# 4040M_v1_0.net
KiCad netlist of a schematic drawn in EasyEDA Pro
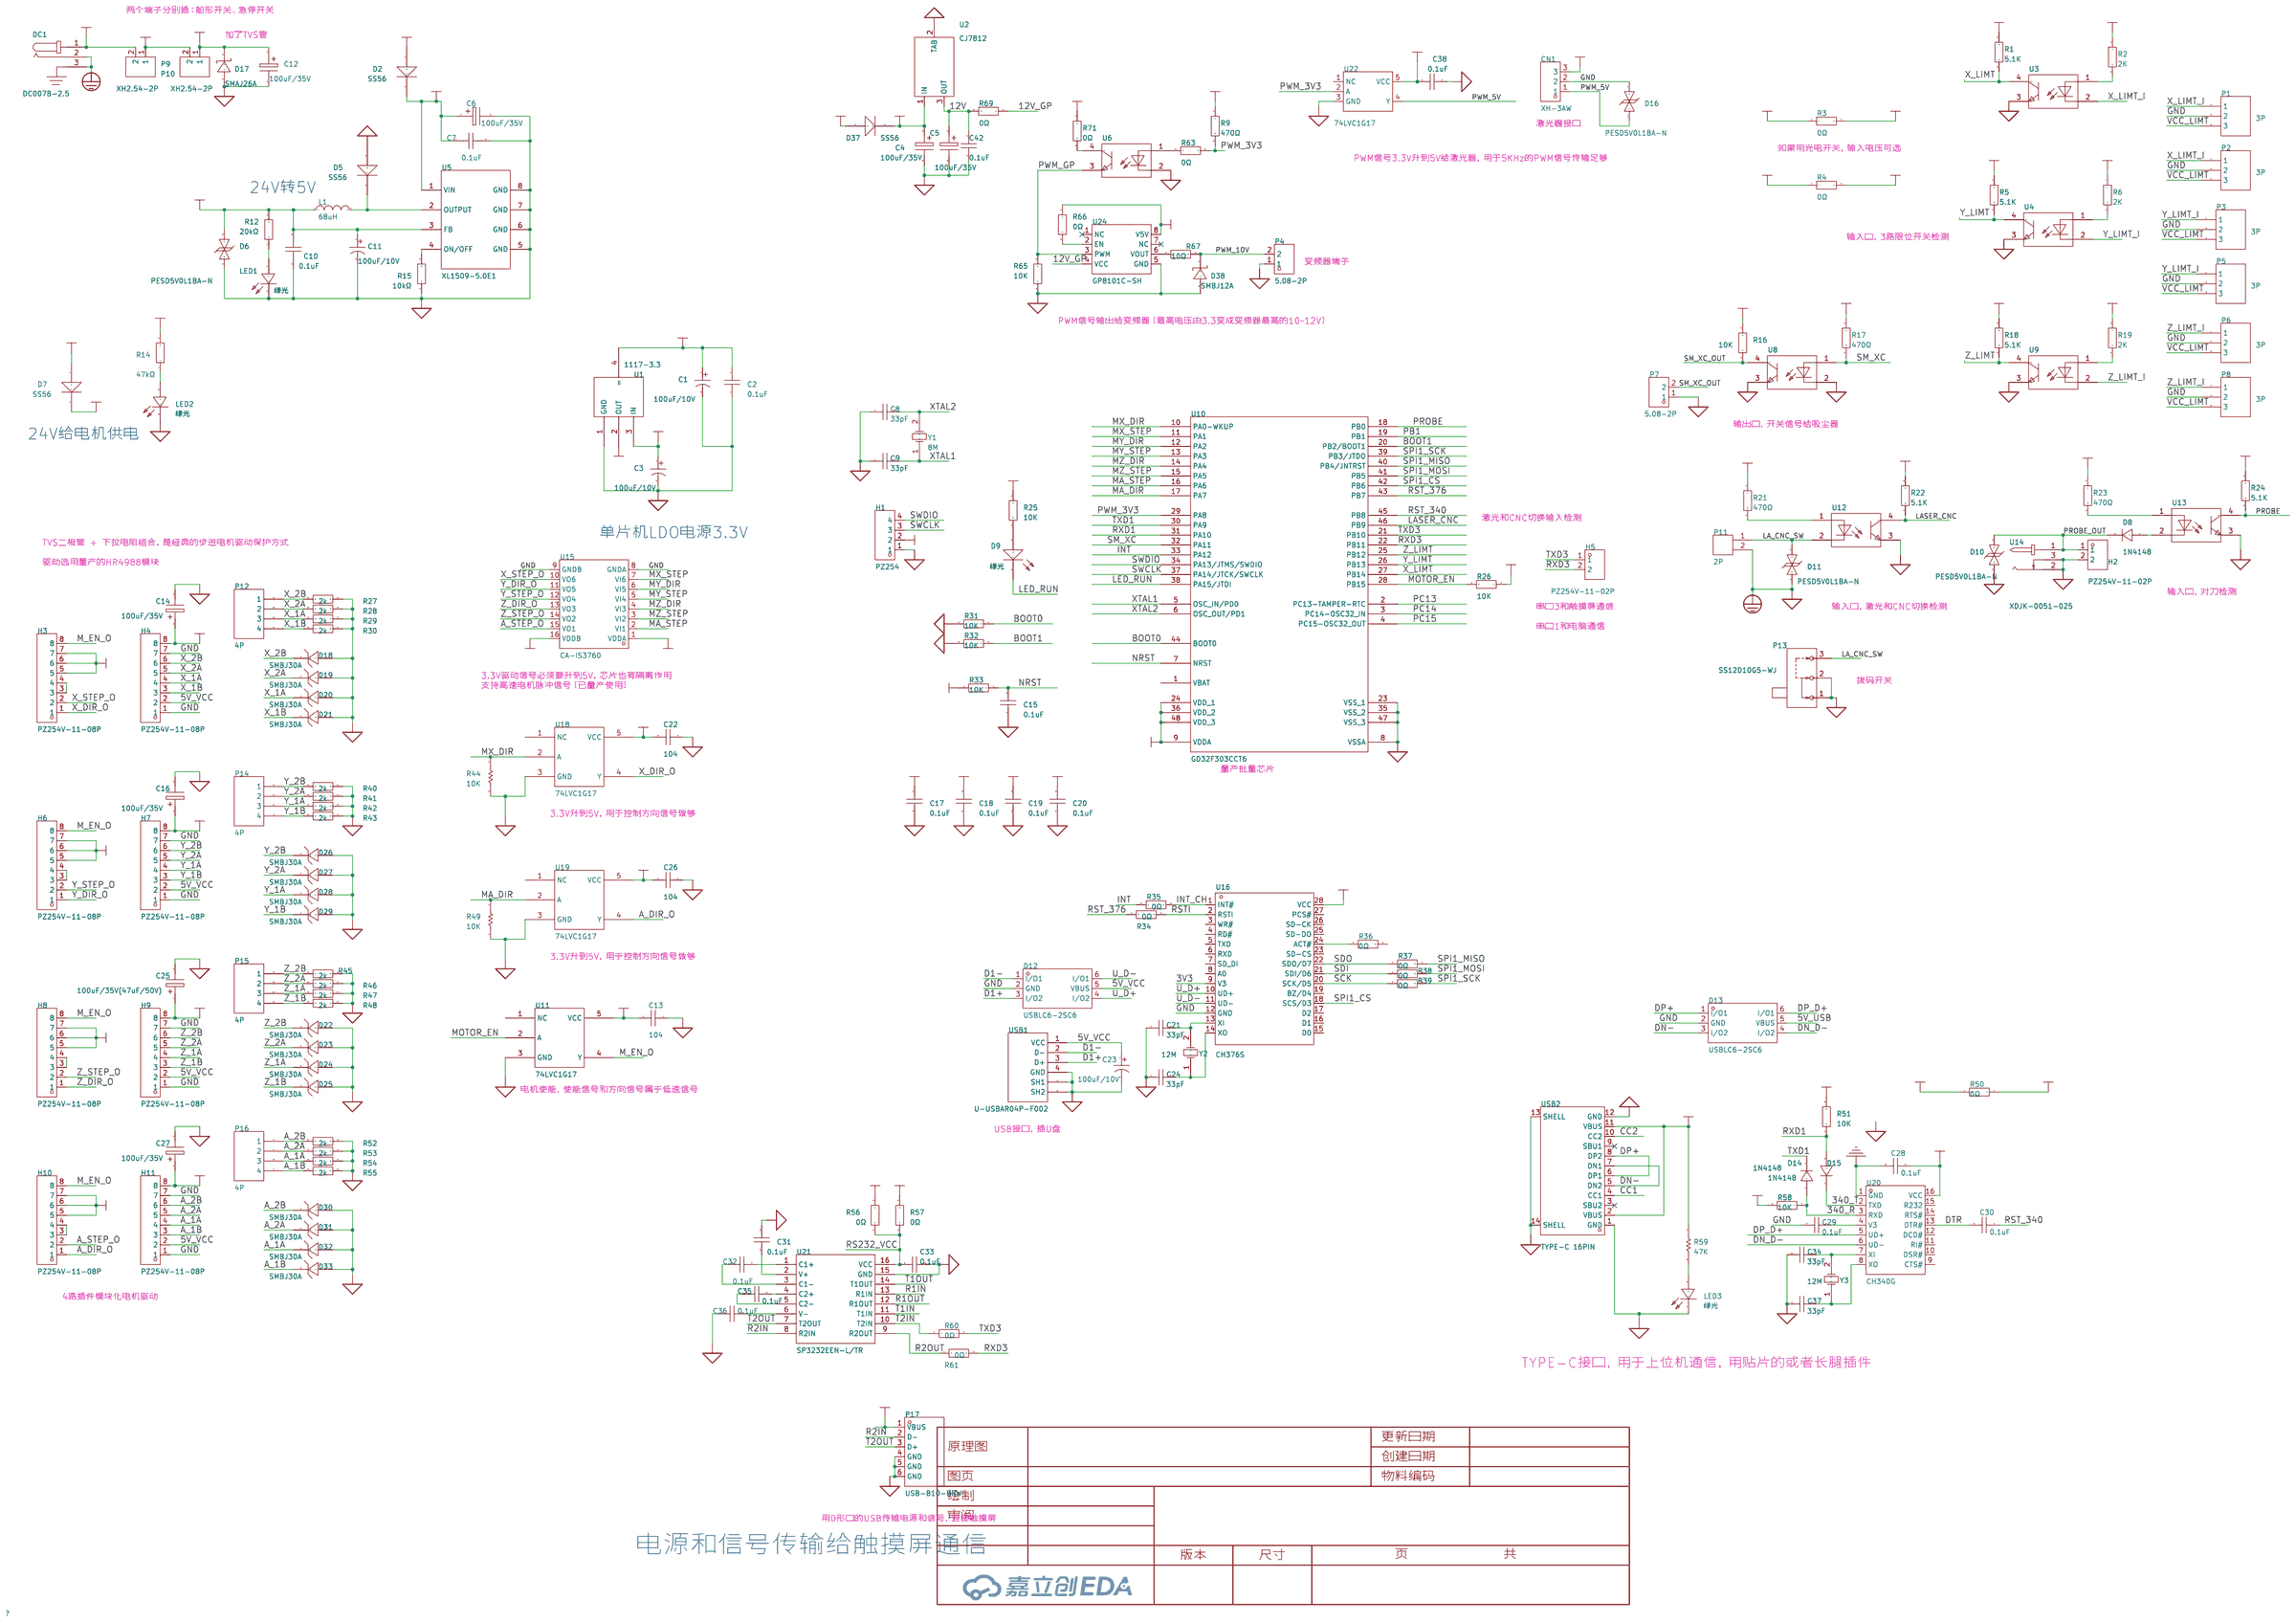
[diagram p0: schematic sheet]

(export (version "E")
  (design (tool "Eeschema 10.0.6"))
  (components
    (comp (ref "C1")
      (value "100uF/10V")
      (footprint "easyedapro:CAP-SMD_BD5.0-L5.3-W5.3-RD")
      (fields (field (name "Manufacturer Part") "CS1A101M-CRD54") (field (name "Manufacturer") "ST(先科)"))
      (libsource (lib "easyedapro") (part "CS1A101M-CRD54"))
    )
    (comp (ref "C2")
      (value "0.1uF")
      (footprint "easyedapro:C0603")
      (description "容值:6.8nF;精度:±10%;额定电压:50V;温度系数:X7R;")
      (fields (field (name "Manufacturer Part") "0603B682K500NT") (field (name "Manufacturer") "FH(风华)"))
      (libsource (lib "easyedapro") (part "0603B682K500NT"))
    )
    (comp (ref "C3")
      (value "100uF/10V")
      (footprint "easyedapro:CAP-SMD_BD5.0-L5.3-W5.3-RD")
      (fields (field (name "Manufacturer Part") "CS1A101M-CRD54") (field (name "Manufacturer") "ST(先科)"))
      (libsource (lib "easyedapro") (part "CS1A101M-CRD54"))
    )
    (comp (ref "C4")
      (value "100uF/35V")
      (footprint "easyedapro:电解电容贴片10x10")
      (libsource (lib "easyedapro") (part "ELECTRO1"))
    )
    (comp (ref "C5")
      (value "100uF/35V")
      (footprint "easyedapro:电解电容贴片10x10")
      (libsource (lib "easyedapro") (part "ELECTRO1"))
    )
    (comp (ref "C6")
      (value "100uF/35V")
      (footprint "easyedapro:电解电容贴片10x10")
      (libsource (lib "easyedapro") (part "ELECTRO1"))
    )
    (comp (ref "C7")
      (value "0.1uF")
      (footprint "easyedapro:C0603")
      (description "容值:8.2nF;精度:±10%;额定电压:50V;温度系数:X7R;")
      (fields (field (name "Manufacturer Part") "0603B822K500NT") (field (name "Manufacturer") "FH(风华)"))
      (libsource (lib "easyedapro") (part "0603B822K500NT"))
    )
    (comp (ref "C8")
      (value "33pF")
      (footprint "easyedapro:C0603")
      (description "容值:12pF;精度:±5%;额定电压:50V;温度系数:C0G;")
      (fields
        (field (name "Manufacturer Part") "CL10C120JB8NNNC")
        (field (name "Manufacturer") "SAMSUNG(三星)")
      )
      (libsource (lib "easyedapro") (part "CL10C120JB8NNNC"))
    )
    (comp (ref "C9")
      (value "33pF")
      (footprint "easyedapro:C0603")
      (description "容值:12pF;精度:±5%;额定电压:50V;温度系数:C0G;")
      (fields
        (field (name "Manufacturer Part") "CL10C120JB8NNNC")
        (field (name "Manufacturer") "SAMSUNG(三星)")
      )
      (libsource (lib "easyedapro") (part "CL10C120JB8NNNC"))
    )
    (comp (ref "C10")
      (value "0.1uF")
      (footprint "easyedapro:C0603")
      (description "容值:8.2nF;精度:±10%;额定电压:50V;温度系数:X7R;")
      (fields (field (name "Manufacturer Part") "0603B822K500NT") (field (name "Manufacturer") "FH(风华)"))
      (libsource (lib "easyedapro") (part "0603B822K500NT"))
    )
    (comp (ref "C11")
      (value "100uF/10V")
      (footprint "easyedapro:CAP-SMD_BD5.0-L5.3-W5.3-RD")
      (fields (field (name "Manufacturer Part") "CS1A101M-CRD54") (field (name "Manufacturer") "ST(先科)"))
      (libsource (lib "easyedapro") (part "CS1A101M-CRD54"))
    )
    (comp (ref "C12")
      (value "100uF/35V")
      (footprint "easyedapro:电解电容贴片10x10")
      (libsource (lib "easyedapro") (part "ELECTRO1"))
    )
    (comp (ref "C13")
      (value "104")
      (footprint "easyedapro:0603C")
      (description "Capacitor (Semiconductor SIM Model)")
      (libsource (lib "easyedapro") (part "Cap Semi"))
    )
    (comp (ref "C14")
      (value "100uF/35V")
      (footprint "easyedapro:电解电容贴片10x10")
      (libsource (lib "easyedapro") (part "ELECTRO1"))
    )
    (comp (ref "C15")
      (value "0.1uF")
      (footprint "easyedapro:C0603")
      (description "容值:6.8nF;精度:±10%;额定电压:50V;温度系数:X7R;")
      (fields (field (name "Manufacturer Part") "0603B682K500NT") (field (name "Manufacturer") "FH(风华)"))
      (libsource (lib "easyedapro") (part "0603B682K500NT"))
    )
    (comp (ref "C16")
      (value "100uF/35V")
      (footprint "easyedapro:电解电容贴片10x10")
      (libsource (lib "easyedapro") (part "ELECTRO1"))
    )
    (comp (ref "C17")
      (value "0.1uF")
      (footprint "easyedapro:C0603")
      (description "容值:6.8nF;精度:±10%;额定电压:50V;温度系数:X7R;")
      (fields (field (name "Manufacturer Part") "0603B682K500NT") (field (name "Manufacturer") "FH(风华)"))
      (libsource (lib "easyedapro") (part "0603B682K500NT"))
    )
    (comp (ref "C18")
      (value "0.1uF")
      (footprint "easyedapro:C0603")
      (description "容值:6.8nF;精度:±10%;额定电压:50V;温度系数:X7R;")
      (fields (field (name "Manufacturer Part") "0603B682K500NT") (field (name "Manufacturer") "FH(风华)"))
      (libsource (lib "easyedapro") (part "0603B682K500NT"))
    )
    (comp (ref "C19")
      (value "0.1uF")
      (footprint "easyedapro:C0603")
      (description "容值:6.8nF;精度:±10%;额定电压:50V;温度系数:X7R;")
      (fields (field (name "Manufacturer Part") "0603B682K500NT") (field (name "Manufacturer") "FH(风华)"))
      (libsource (lib "easyedapro") (part "0603B682K500NT"))
    )
    (comp (ref "C20")
      (value "0.1uF")
      (footprint "easyedapro:C0603")
      (description "容值:6.8nF;精度:±10%;额定电压:50V;温度系数:X7R;")
      (fields (field (name "Manufacturer Part") "0603B682K500NT") (field (name "Manufacturer") "FH(风华)"))
      (libsource (lib "easyedapro") (part "0603B682K500NT"))
    )
    (comp (ref "C21")
      (value "33pF")
      (footprint "easyedapro:C0603")
      (description "容值:12pF;精度:±5%;额定电压:50V;温度系数:C0G;")
      (fields
        (field (name "Manufacturer Part") "CL10C120JB8NNNC")
        (field (name "Manufacturer") "SAMSUNG(三星)")
      )
      (libsource (lib "easyedapro") (part "CL10C120JB8NNNC"))
    )
    (comp (ref "C22")
      (value "104")
      (footprint "easyedapro:0603C")
      (description "Capacitor (Semiconductor SIM Model)")
      (libsource (lib "easyedapro") (part "Cap Semi"))
    )
    (comp (ref "C23")
      (value "100uF/10V")
      (footprint "easyedapro:CAP-SMD_BD5.0-L5.3-W5.3-RD")
      (fields (field (name "Manufacturer Part") "CS1A101M-CRD54") (field (name "Manufacturer") "ST(先科)"))
      (libsource (lib "easyedapro") (part "CS1A101M-CRD54"))
    )
    (comp (ref "C24")
      (value "33pF")
      (footprint "easyedapro:C0603")
      (description "容值:12pF;精度:±5%;额定电压:50V;温度系数:C0G;")
      (fields
        (field (name "Manufacturer Part") "CL10C120JB8NNNC")
        (field (name "Manufacturer") "SAMSUNG(三星)")
      )
      (libsource (lib "easyedapro") (part "CL10C120JB8NNNC"))
    )
    (comp (ref "C25")
      (value "100uF/35V(47uF/50V)")
      (footprint "easyedapro:电解电容贴片10x10")
      (libsource (lib "easyedapro") (part "ELECTRO1"))
    )
    (comp (ref "C26")
      (value "104")
      (footprint "easyedapro:0603C")
      (description "Capacitor (Semiconductor SIM Model)")
      (libsource (lib "easyedapro") (part "Cap Semi"))
    )
    (comp (ref "C27")
      (value "100uF/35V")
      (footprint "easyedapro:电解电容贴片10x10")
      (libsource (lib "easyedapro") (part "ELECTRO1"))
    )
    (comp (ref "C28")
      (value "0.1uF")
      (footprint "easyedapro:C0603")
      (description "容值:6.8nF;精度:±10%;额定电压:50V;温度系数:X7R;")
      (fields (field (name "Manufacturer Part") "0603B682K500NT") (field (name "Manufacturer") "FH(风华)"))
      (libsource (lib "easyedapro") (part "0603B682K500NT"))
    )
    (comp (ref "C29")
      (value "0.1uF")
      (footprint "easyedapro:C0603")
      (description "容值:6.8nF;精度:±10%;额定电压:50V;温度系数:X7R;")
      (fields (field (name "Manufacturer Part") "0603B682K500NT") (field (name "Manufacturer") "FH(风华)"))
      (libsource (lib "easyedapro") (part "0603B682K500NT"))
    )
    (comp (ref "C30")
      (value "0.1uF")
      (footprint "easyedapro:C0603")
      (description "容值:6.8nF;精度:±10%;额定电压:50V;温度系数:X7R;")
      (fields (field (name "Manufacturer Part") "0603B682K500NT") (field (name "Manufacturer") "FH(风华)"))
      (libsource (lib "easyedapro") (part "0603B682K500NT"))
    )
    (comp (ref "C31")
      (value "0.1uF")
      (footprint "easyedapro:C0603")
      (description "容值:6.8nF;精度:±10%;额定电压:50V;温度系数:X7R;")
      (fields (field (name "Manufacturer Part") "0603B682K500NT") (field (name "Manufacturer") "FH(风华)"))
      (libsource (lib "easyedapro") (part "0603B682K500NT"))
    )
    (comp (ref "C32")
      (value "0.1uF")
      (footprint "easyedapro:C0603")
      (description "容值:6.8nF;精度:±10%;额定电压:50V;温度系数:X7R;")
      (fields (field (name "Manufacturer Part") "0603B682K500NT") (field (name "Manufacturer") "FH(风华)"))
      (libsource (lib "easyedapro") (part "0603B682K500NT"))
    )
    (comp (ref "C33")
      (value "0.1uF")
      (footprint "easyedapro:C0603")
      (description "容值:6.8nF;精度:±10%;额定电压:50V;温度系数:X7R;")
      (fields (field (name "Manufacturer Part") "0603B682K500NT") (field (name "Manufacturer") "FH(风华)"))
      (libsource (lib "easyedapro") (part "0603B682K500NT"))
    )
    (comp (ref "C34")
      (value "33pF")
      (footprint "easyedapro:C0603")
      (description "容值:12pF;精度:±5%;额定电压:50V;温度系数:C0G;")
      (fields
        (field (name "Manufacturer Part") "CL10C120JB8NNNC")
        (field (name "Manufacturer") "SAMSUNG(三星)")
      )
      (libsource (lib "easyedapro") (part "CL10C120JB8NNNC"))
    )
    (comp (ref "C35")
      (value "0.1uF")
      (footprint "easyedapro:C0603")
      (description "容值:6.8nF;精度:±10%;额定电压:50V;温度系数:X7R;")
      (fields (field (name "Manufacturer Part") "0603B682K500NT") (field (name "Manufacturer") "FH(风华)"))
      (libsource (lib "easyedapro") (part "0603B682K500NT"))
    )
    (comp (ref "C36")
      (value "0.1uF")
      (footprint "easyedapro:C0603")
      (description "容值:6.8nF;精度:±10%;额定电压:50V;温度系数:X7R;")
      (fields (field (name "Manufacturer Part") "0603B682K500NT") (field (name "Manufacturer") "FH(风华)"))
      (libsource (lib "easyedapro") (part "0603B682K500NT"))
    )
    (comp (ref "C37")
      (value "33pF")
      (footprint "easyedapro:C0603")
      (description "容值:12pF;精度:±5%;额定电压:50V;温度系数:C0G;")
      (fields
        (field (name "Manufacturer Part") "CL10C120JB8NNNC")
        (field (name "Manufacturer") "SAMSUNG(三星)")
      )
      (libsource (lib "easyedapro") (part "CL10C120JB8NNNC"))
    )
    (comp (ref "C38")
      (value "0.1uF")
      (footprint "easyedapro:C0603")
      (description "容值:6.8nF;精度:±10%;额定电压:50V;温度系数:X7R;")
      (fields (field (name "Manufacturer Part") "0603B682K500NT") (field (name "Manufacturer") "FH(风华)"))
      (libsource (lib "easyedapro") (part "0603B682K500NT"))
    )
    (comp (ref "C42")
      (value "0.1uF")
      (footprint "easyedapro:C0603")
      (description "容值:6.8nF;精度:±10%;额定电压:50V;温度系数:X7R;")
      (fields (field (name "Manufacturer Part") "0603B682K500NT") (field (name "Manufacturer") "FH(风华)"))
      (libsource (lib "easyedapro") (part "0603B682K500NT"))
    )
    (comp (ref "CN1")
      (value "XH-3AW")
      (footprint "easyedapro:CONN-TH_3P-P2.54_HCTL_XH-3AW")
      (fields (field (name "Manufacturer") "HCTL(华灿天禄)"))
      (libsource (lib "easyedapro") (part "XH-3AW_C2908612"))
    )
    (comp (ref "D2")
      (value "SS56")
      (footprint "easyedapro:SMA")
      (libsource (lib "easyedapro") (part "1N4148"))
    )
    (comp (ref "D5")
      (value "SS56")
      (footprint "easyedapro:SMA")
      (libsource (lib "easyedapro") (part "1N4148"))
    )
    (comp (ref "D6")
      (value "PESD5V0L1BA-N")
      (footprint "easyedapro:SOD-523_L1.2-W0.8-LS1.6-BI")
      (description "极性:Bidirectional;反向关断电压（典型值）:5V (Max);击穿电压（最小值）:6V;箝位电压:15V;峰值脉冲电流（10/1000us）:5A (8/20us);")
      (fields (field (name "Manufacturer") "BORN伯恩半导体"))
      (libsource (lib "easyedapro") (part "PESD5V0S1BBN"))
    )
    (comp (ref "D7")
      (value "SS56")
      (footprint "easyedapro:SMA")
      (libsource (lib "easyedapro") (part "1N4148"))
    )
    (comp (ref "D8")
      (value "1N4148")
      (footprint "easyedapro:SOD-323_L1.8-W1.3-LS2.5-RD")
      (description "二极管配置:独立式;正向压降(Vf):1.25V@150mA;直流反向耐压(Vr):100V;整流电流:150mA;反向恢复时间(Trr):4ns;")
      (fields (field (name "Manufacturer") "CJ(江苏长电/长晶)"))
      (libsource (lib "easyedapro") (part "1N4148WS T4"))
    )
    (comp (ref "D9")
      (value "绿光")
      (footprint "easyedapro:0603LED")
      (libsource (lib "easyedapro") (part "LED"))
    )
    (comp (ref "D10")
      (value "PESD5V0L1BA-N")
      (footprint "easyedapro:SOD-523_L1.2-W0.8-LS1.6-BI")
      (description "极性:Bidirectional;反向关断电压（典型值）:5V (Max);击穿电压（最小值）:6V;箝位电压:15V;峰值脉冲电流（10/1000us）:5A (8/20us);")
      (fields (field (name "Manufacturer") "BORN伯恩半导体"))
      (libsource (lib "easyedapro") (part "PESD5V0S1BBN"))
    )
    (comp (ref "D11")
      (value "PESD5V0L1BA-N")
      (footprint "easyedapro:SOD-523_L1.2-W0.8-LS1.6-BI")
      (description "极性:Bidirectional;反向关断电压（典型值）:5V (Max);击穿电压（最小值）:6V;箝位电压:15V;峰值脉冲电流（10/1000us）:5A (8/20us);")
      (fields (field (name "Manufacturer") "BORN伯恩半导体"))
      (libsource (lib "easyedapro") (part "PESD5V0S1BBN"))
    )
    (comp (ref "D12")
      (value "USBLC6-2SC6")
      (footprint "easyedapro:SOT-23-6_L2.9-W1.6-P0.95-LS2.8-BL")
      (description "最大钳位电压:15V;击穿电压:6V;")
      (fields (field (name "Manufacturer") "UMW(友台半导体)"))
      (libsource (lib "easyedapro") (part "USBLC6-2SC6_C2687116"))
    )
    (comp (ref "D13")
      (value "USBLC6-2SC6")
      (footprint "easyedapro:SOT-23-6_L2.9-W1.6-P0.95-LS2.8-BL")
      (description "最大钳位电压:15V;击穿电压:6V;")
      (fields (field (name "Manufacturer") "UMW(友台半导体)"))
      (libsource (lib "easyedapro") (part "USBLC6-2SC6_C2687116"))
    )
    (comp (ref "D14")
      (value "1N4148")
      (footprint "easyedapro:SOD-323_L1.8-W1.3-LS2.5-RD")
      (description "二极管配置:独立式;正向压降(Vf):1.25V@150mA;直流反向耐压(Vr):100V;整流电流:150mA;反向恢复时间(Trr):4ns;")
      (fields (field (name "Manufacturer") "CJ(江苏长电/长晶)"))
      (libsource (lib "easyedapro") (part "1N4148WS T4"))
    )
    (comp (ref "D15")
      (value "1N4148")
      (footprint "easyedapro:SOD-323_L1.8-W1.3-LS2.5-RD")
      (description "二极管配置:独立式;正向压降(Vf):1.25V@150mA;直流反向耐压(Vr):100V;整流电流:150mA;反向恢复时间(Trr):4ns;")
      (fields (field (name "Manufacturer") "CJ(江苏长电/长晶)"))
      (libsource (lib "easyedapro") (part "1N4148WS T4"))
    )
    (comp (ref "D16")
      (value "PESD5V0L1BA-N")
      (footprint "easyedapro:SOD-523_L1.2-W0.8-LS1.6-BI")
      (description "极性:Bidirectional;反向关断电压（典型值）:5V (Max);击穿电压（最小值）:6V;箝位电压:15V;峰值脉冲电流（10/1000us）:5A (8/20us);")
      (fields (field (name "Manufacturer") "BORN伯恩半导体"))
      (libsource (lib "easyedapro") (part "PESD5V0S1BBN"))
    )
    (comp (ref "D17")
      (value "SMAJ26A")
      (footprint "easyedapro:SMA_L4.4-W2.8-LS5.1-RD")
      (description "反向截止电压(Vrwm):26V;最大钳位电压:42.1V;峰值脉冲电流(Ipp):9.5A;击穿电压:28.9V;")
      (fields (field (name "Manufacturer") "JJW(捷捷微)"))
      (libsource (lib "easyedapro") (part "SMAJ26A_C356747"))
    )
    (comp (ref "D18")
      (value "SMBJ30A")
      (footprint "easyedapro:SMB_L4.6-W3.6-LS5.3-RD")
      (description "反向截止电压(Vrwm):30V;最大钳位电压:48.4V;峰值脉冲电流(Ipp):12.4A;击穿电压:33.3V;")
      (fields (field (name "Manufacturer") "GOOD-ARK(固锝)"))
      (libsource (lib "easyedapro") (part "SMBJ30A_C266337"))
    )
    (comp (ref "D19")
      (value "SMBJ30A")
      (footprint "easyedapro:SMB_L4.6-W3.6-LS5.3-RD")
      (description "反向截止电压(Vrwm):30V;最大钳位电压:48.4V;峰值脉冲电流(Ipp):12.4A;击穿电压:33.3V;")
      (fields (field (name "Manufacturer") "GOOD-ARK(固锝)"))
      (libsource (lib "easyedapro") (part "SMBJ30A_C266337"))
    )
    (comp (ref "D20")
      (value "SMBJ30A")
      (footprint "easyedapro:SMB_L4.6-W3.6-LS5.3-RD")
      (description "反向截止电压(Vrwm):30V;最大钳位电压:48.4V;峰值脉冲电流(Ipp):12.4A;击穿电压:33.3V;")
      (fields (field (name "Manufacturer") "GOOD-ARK(固锝)"))
      (libsource (lib "easyedapro") (part "SMBJ30A_C266337"))
    )
    (comp (ref "D21")
      (value "SMBJ30A")
      (footprint "easyedapro:SMB_L4.6-W3.6-LS5.3-RD")
      (description "反向截止电压(Vrwm):30V;最大钳位电压:48.4V;峰值脉冲电流(Ipp):12.4A;击穿电压:33.3V;")
      (fields (field (name "Manufacturer") "GOOD-ARK(固锝)"))
      (libsource (lib "easyedapro") (part "SMBJ30A_C266337"))
    )
    (comp (ref "D22")
      (value "SMBJ30A")
      (footprint "easyedapro:SMB_L4.6-W3.6-LS5.3-RD")
      (description "反向截止电压(Vrwm):30V;最大钳位电压:48.4V;峰值脉冲电流(Ipp):12.4A;击穿电压:33.3V;")
      (fields (field (name "Manufacturer") "GOOD-ARK(固锝)"))
      (libsource (lib "easyedapro") (part "SMBJ30A_C266337"))
    )
    (comp (ref "D23")
      (value "SMBJ30A")
      (footprint "easyedapro:SMB_L4.6-W3.6-LS5.3-RD")
      (description "反向截止电压(Vrwm):30V;最大钳位电压:48.4V;峰值脉冲电流(Ipp):12.4A;击穿电压:33.3V;")
      (fields (field (name "Manufacturer") "GOOD-ARK(固锝)"))
      (libsource (lib "easyedapro") (part "SMBJ30A_C266337"))
    )
    (comp (ref "D24")
      (value "SMBJ30A")
      (footprint "easyedapro:SMB_L4.6-W3.6-LS5.3-RD")
      (description "反向截止电压(Vrwm):30V;最大钳位电压:48.4V;峰值脉冲电流(Ipp):12.4A;击穿电压:33.3V;")
      (fields (field (name "Manufacturer") "GOOD-ARK(固锝)"))
      (libsource (lib "easyedapro") (part "SMBJ30A_C266337"))
    )
    (comp (ref "D25")
      (value "SMBJ30A")
      (footprint "easyedapro:SMB_L4.6-W3.6-LS5.3-RD")
      (description "反向截止电压(Vrwm):30V;最大钳位电压:48.4V;峰值脉冲电流(Ipp):12.4A;击穿电压:33.3V;")
      (fields (field (name "Manufacturer") "GOOD-ARK(固锝)"))
      (libsource (lib "easyedapro") (part "SMBJ30A_C266337"))
    )
    (comp (ref "D26")
      (value "SMBJ30A")
      (footprint "easyedapro:SMB_L4.6-W3.6-LS5.3-RD")
      (description "反向截止电压(Vrwm):30V;最大钳位电压:48.4V;峰值脉冲电流(Ipp):12.4A;击穿电压:33.3V;")
      (fields (field (name "Manufacturer") "GOOD-ARK(固锝)"))
      (libsource (lib "easyedapro") (part "SMBJ30A_C266337"))
    )
    (comp (ref "D27")
      (value "SMBJ30A")
      (footprint "easyedapro:SMB_L4.6-W3.6-LS5.3-RD")
      (description "反向截止电压(Vrwm):30V;最大钳位电压:48.4V;峰值脉冲电流(Ipp):12.4A;击穿电压:33.3V;")
      (fields (field (name "Manufacturer") "GOOD-ARK(固锝)"))
      (libsource (lib "easyedapro") (part "SMBJ30A_C266337"))
    )
    (comp (ref "D28")
      (value "SMBJ30A")
      (footprint "easyedapro:SMB_L4.6-W3.6-LS5.3-RD")
      (description "反向截止电压(Vrwm):30V;最大钳位电压:48.4V;峰值脉冲电流(Ipp):12.4A;击穿电压:33.3V;")
      (fields (field (name "Manufacturer") "GOOD-ARK(固锝)"))
      (libsource (lib "easyedapro") (part "SMBJ30A_C266337"))
    )
    (comp (ref "D29")
      (value "SMBJ30A")
      (footprint "easyedapro:SMB_L4.6-W3.6-LS5.3-RD")
      (description "反向截止电压(Vrwm):30V;最大钳位电压:48.4V;峰值脉冲电流(Ipp):12.4A;击穿电压:33.3V;")
      (fields (field (name "Manufacturer") "GOOD-ARK(固锝)"))
      (libsource (lib "easyedapro") (part "SMBJ30A_C266337"))
    )
    (comp (ref "D30")
      (value "SMBJ30A")
      (footprint "easyedapro:SMB_L4.6-W3.6-LS5.3-RD")
      (description "反向截止电压(Vrwm):30V;最大钳位电压:48.4V;峰值脉冲电流(Ipp):12.4A;击穿电压:33.3V;")
      (fields (field (name "Manufacturer") "GOOD-ARK(固锝)"))
      (libsource (lib "easyedapro") (part "SMBJ30A_C266337"))
    )
    (comp (ref "D31")
      (value "SMBJ30A")
      (footprint "easyedapro:SMB_L4.6-W3.6-LS5.3-RD")
      (description "反向截止电压(Vrwm):30V;最大钳位电压:48.4V;峰值脉冲电流(Ipp):12.4A;击穿电压:33.3V;")
      (fields (field (name "Manufacturer") "GOOD-ARK(固锝)"))
      (libsource (lib "easyedapro") (part "SMBJ30A_C266337"))
    )
    (comp (ref "D32")
      (value "SMBJ30A")
      (footprint "easyedapro:SMB_L4.6-W3.6-LS5.3-RD")
      (description "反向截止电压(Vrwm):30V;最大钳位电压:48.4V;峰值脉冲电流(Ipp):12.4A;击穿电压:33.3V;")
      (fields (field (name "Manufacturer") "GOOD-ARK(固锝)"))
      (libsource (lib "easyedapro") (part "SMBJ30A_C266337"))
    )
    (comp (ref "D33")
      (value "SMBJ30A")
      (footprint "easyedapro:SMB_L4.6-W3.6-LS5.3-RD")
      (description "反向截止电压(Vrwm):30V;最大钳位电压:48.4V;峰值脉冲电流(Ipp):12.4A;击穿电压:33.3V;")
      (fields (field (name "Manufacturer") "GOOD-ARK(固锝)"))
      (libsource (lib "easyedapro") (part "SMBJ30A_C266337"))
    )
    (comp (ref "D37")
      (value "SS56")
      (footprint "easyedapro:SMA")
      (libsource (lib "easyedapro") (part "1N4148"))
    )
    (comp (ref "D38")
      (value "SMBJ12A")
      (footprint "easyedapro:SMB_L4.6-W3.6-LS5.4-RD")
      (description "反向截止电压(Vrwm):12V;最大钳位电压:19.9V;峰值脉冲电流(Ipp):30.2A;击穿电压:13.3V;")
      (fields (field (name "Manufacturer") "JJW(捷捷微)"))
      (libsource (lib "easyedapro") (part "SMBJ12A_C356757"))
    )
    (comp (ref "DC1")
      (value "DC007B-2.5")
      (footprint "easyedapro:DC-IN-TH_HX-DC007B-2.5")
      (description "连接器类型:DC电源插座;安装方式:弯插;触点内径:2.5mm;触点外径:7.7mm;额定电流:5A;额定电压:20V;工作温度:-25°C~+70°C;")
      (fields (field (name "Manufacturer") "SHOU HAN(首韩)"))
      (libsource (lib "easyedapro") (part "DC007B-2.5"))
    )
    (comp (ref "H1")
      (value "PZ254")
      (footprint "easyedapro:HDR-TH_4P-P2.54-V-M")
      (fields (field (name "Manufacturer") "XFCN(兴飞)"))
      (libsource (lib "easyedapro") (part "PZ254V-11-04P_C2691448"))
    )
    (comp (ref "H2")
      (value "PZ254V-11-02P")
      (footprint "easyedapro:HDR-TH_2P-P2.54-V-M")
      (fields (field (name "Manufacturer") "XFCN(兴飞)"))
      (libsource (lib "easyedapro") (part "PZ254V-11-02P"))
    )
    (comp (ref "H3")
      (value "PZ254V-11-08P")
      (footprint "easyedapro:HDR-TH_8P-P2.54-V-M")
      (fields (field (name "Manufacturer") "XFCN(兴飞)"))
      (libsource (lib "easyedapro") (part "PZ254V-11-08P"))
    )
    (comp (ref "H4")
      (value "PZ254V-11-08P")
      (footprint "easyedapro:HDR-TH_8P-P2.54-V-M")
      (fields (field (name "Manufacturer") "XFCN(兴飞)"))
      (libsource (lib "easyedapro") (part "PZ254V-11-08P"))
    )
    (comp (ref "H5")
      (value "PZ254V-11-02P")
      (footprint "easyedapro:HDR-TH_2P-P2.54-V-M")
      (fields (field (name "Manufacturer") "XFCN(兴飞)"))
      (libsource (lib "easyedapro") (part "PZ254V-11-02P"))
    )
    (comp (ref "H6")
      (value "PZ254V-11-08P")
      (footprint "easyedapro:HDR-TH_8P-P2.54-V-M")
      (fields (field (name "Manufacturer") "XFCN(兴飞)"))
      (libsource (lib "easyedapro") (part "PZ254V-11-08P"))
    )
    (comp (ref "H7")
      (value "PZ254V-11-08P")
      (footprint "easyedapro:HDR-TH_8P-P2.54-V-M")
      (fields (field (name "Manufacturer") "XFCN(兴飞)"))
      (libsource (lib "easyedapro") (part "PZ254V-11-08P"))
    )
    (comp (ref "H8")
      (value "PZ254V-11-08P")
      (footprint "easyedapro:HDR-TH_8P-P2.54-V-M")
      (fields (field (name "Manufacturer") "XFCN(兴飞)"))
      (libsource (lib "easyedapro") (part "PZ254V-11-08P"))
    )
    (comp (ref "H9")
      (value "PZ254V-11-08P")
      (footprint "easyedapro:HDR-TH_8P-P2.54-V-M")
      (fields (field (name "Manufacturer") "XFCN(兴飞)"))
      (libsource (lib "easyedapro") (part "PZ254V-11-08P"))
    )
    (comp (ref "H10")
      (value "PZ254V-11-08P")
      (footprint "easyedapro:HDR-TH_8P-P2.54-V-M")
      (fields (field (name "Manufacturer") "XFCN(兴飞)"))
      (libsource (lib "easyedapro") (part "PZ254V-11-08P"))
    )
    (comp (ref "H11")
      (value "PZ254V-11-08P")
      (footprint "easyedapro:HDR-TH_8P-P2.54-V-M")
      (fields (field (name "Manufacturer") "XFCN(兴飞)"))
      (libsource (lib "easyedapro") (part "PZ254V-11-08P"))
    )
    (comp (ref "L1")
      (value "68uH")
      (footprint "easyedapro:IND-SMD_L7.0-W7.0_SMDRI74-330MT")
      (description "电感值:33uH;精度:±20%;额定电流:960mA;饱和电流(Isat):1.8A;类型:屏蔽电感;")
      (fields (field (name "Manufacturer Part") "SMDRI74-330MT") (field (name "Manufacturer") "SXN(顺翔诺)"))
      (libsource (lib "easyedapro") (part "SMDRI74-330MT"))
    )
    (comp (ref "LED1")
      (value "绿光")
      (footprint "easyedapro:LED0603-RD")
      (fields (field (name "Manufacturer") "KENTO"))
      (libsource (lib "easyedapro") (part "KT-0603R"))
    )
    (comp (ref "LED2")
      (value "绿光")
      (footprint "easyedapro:LED0603-RD")
      (fields (field (name "Manufacturer") "KENTO"))
      (libsource (lib "easyedapro") (part "KT-0603R"))
    )
    (comp (ref "LED3")
      (value "绿光")
      (footprint "easyedapro:LED0603-RD")
      (fields (field (name "Manufacturer") "KENTO"))
      (libsource (lib "easyedapro") (part "KT-0603R"))
    )
    (comp (ref "P1")
      (value "3P")
      (footprint "easyedapro:HDR1X3_CON")
      (libsource (lib "easyedapro") (part "3P"))
    )
    (comp (ref "P2")
      (value "3P")
      (footprint "easyedapro:HDR1X3_CON")
      (libsource (lib "easyedapro") (part "3P"))
    )
    (comp (ref "P3")
      (value "3P")
      (footprint "easyedapro:HDR1X3_CON")
      (libsource (lib "easyedapro") (part "3P"))
    )
    (comp (ref "P4")
      (value "5.08-2P")
      (footprint "easyedapro:CONN-TH_KF2EDG15R-5.08-2P")
      (fields (field (name "Manufacturer") "KEFA(科发)"))
      (libsource (lib "easyedapro") (part "KF2EDG15R-5.08-2P"))
    )
    (comp (ref "P5")
      (value "3P")
      (footprint "easyedapro:HDR1X3_CON")
      (libsource (lib "easyedapro") (part "3P"))
    )
    (comp (ref "P6")
      (value "3P")
      (footprint "easyedapro:HDR1X3_CON")
      (libsource (lib "easyedapro") (part "3P"))
    )
    (comp (ref "P7")
      (value "5.08-2P")
      (footprint "easyedapro:CONN-TH_KF2EDG15R-5.08-2P")
      (fields (field (name "Manufacturer") "KEFA(科发)"))
      (libsource (lib "easyedapro") (part "KF2EDG15R-5.08-2P"))
    )
    (comp (ref "P8")
      (value "3P")
      (footprint "easyedapro:HDR1X3_CON")
      (libsource (lib "easyedapro") (part "3P"))
    )
    (comp (ref "P9")
      (value "XH2.54-2P")
      (footprint "easyedapro:CONN-TH_XH2.54-2P")
      (libsource (lib "easyedapro") (part "XH2.54直插座-2P"))
    )
    (comp (ref "P10")
      (value "XH2.54-2P")
      (footprint "easyedapro:CONN-TH_XH2.54-2P")
      (libsource (lib "easyedapro") (part "XH2.54直插座-2P"))
    )
    (comp (ref "P11") (value "2P") (libsource (lib "easyedapro") (part "2P")))
    (comp (ref "P12")
      (value "4P")
      (footprint "easyedapro:HDR1X4_CON")
      (libsource (lib "easyedapro") (part "4P"))
    )
    (comp (ref "P13")
      (value "SS12D10G5-WJ")
      (footprint "easyedapro:SW-TH_3P-SS12D06-1")
      (description "电路结构:单刀双掷;安装方式:弯插;开关颜色:黑色;额定电流:2A;额定电压:125V;工作寿命:3千次;")
      (fields (field (name "Manufacturer") "SHOU HAN(首韩)"))
      (libsource (lib "easyedapro") (part "SS12D10G5-WJ"))
    )
    (comp (ref "P14")
      (value "4P")
      (footprint "easyedapro:HDR1X4_CON")
      (libsource (lib "easyedapro") (part "4P"))
    )
    (comp (ref "P15")
      (value "4P")
      (footprint "easyedapro:HDR1X4_CON")
      (libsource (lib "easyedapro") (part "4P"))
    )
    (comp (ref "P16")
      (value "4P")
      (footprint "easyedapro:HDR1X4_CON")
      (libsource (lib "easyedapro") (part "4P"))
    )
    (comp (ref "P17")
      (value "USB-B10-BRW")
      (footprint "easyedapro:USB-B-TH_USB-B10-BRW")
      (fields (field (name "Manufacturer") "XUNPU(讯普)"))
      (libsource (lib "easyedapro") (part "USB-B10-BRW"))
    )
    (comp (ref "R1")
      (value "47K")
      (footprint "easyedapro:R0603")
      (description "电阻类型:厚膜电阻;阻值:24kΩ;精度:±1%;功率:100mW;工作电压:75V;温度系数:±100ppm/°C;")
      (fields
        (field (name "Manufacturer Part") "0603WAF2402T5E")
        (field (name "Manufacturer") "UNI-ROYAL(厚声)")
      )
      (libsource (lib "easyedapro") (part "0603WAF2402T5E"))
    )
    (comp (ref "R2")
      (value "4.7K")
      (footprint "easyedapro:R0603")
      (description "电阻类型:厚膜电阻;阻值:24kΩ;精度:±1%;功率:100mW;工作电压:75V;温度系数:±100ppm/°C;")
      (fields
        (field (name "Manufacturer Part") "0603WAF2402T5E")
        (field (name "Manufacturer") "UNI-ROYAL(厚声)")
      )
      (libsource (lib "easyedapro") (part "0603WAF2402T5E"))
    )
    (comp (ref "R3")
      (value "0Ω")
      (footprint "easyedapro:R0603")
      (description "电阻类型:厚膜电阻;阻值:24kΩ;精度:±1%;功率:100mW;工作电压:75V;温度系数:±100ppm/°C;")
      (fields
        (field (name "Manufacturer Part") "0603WAF2402T5E")
        (field (name "Manufacturer") "UNI-ROYAL(厚声)")
      )
      (libsource (lib "easyedapro") (part "0603WAF2402T5E"))
    )
    (comp (ref "R4")
      (value "0Ω")
      (footprint "easyedapro:R0603")
      (description "电阻类型:厚膜电阻;阻值:24kΩ;精度:±1%;功率:100mW;工作电压:75V;温度系数:±100ppm/°C;")
      (fields
        (field (name "Manufacturer Part") "0603WAF2402T5E")
        (field (name "Manufacturer") "UNI-ROYAL(厚声)")
      )
      (libsource (lib "easyedapro") (part "0603WAF2402T5E"))
    )
    (comp (ref "R5")
      (value "47K")
      (footprint "easyedapro:R0603")
      (description "电阻类型:厚膜电阻;阻值:24kΩ;精度:±1%;功率:100mW;工作电压:75V;温度系数:±100ppm/°C;")
      (fields
        (field (name "Manufacturer Part") "0603WAF2402T5E")
        (field (name "Manufacturer") "UNI-ROYAL(厚声)")
      )
      (libsource (lib "easyedapro") (part "0603WAF2402T5E"))
    )
    (comp (ref "R6")
      (value "4.7K")
      (footprint "easyedapro:R0603")
      (description "电阻类型:厚膜电阻;阻值:24kΩ;精度:±1%;功率:100mW;工作电压:75V;温度系数:±100ppm/°C;")
      (fields
        (field (name "Manufacturer Part") "0603WAF2402T5E")
        (field (name "Manufacturer") "UNI-ROYAL(厚声)")
      )
      (libsource (lib "easyedapro") (part "0603WAF2402T5E"))
    )
    (comp (ref "R9")
      (value "47K")
      (footprint "easyedapro:R0603")
      (description "电阻类型:厚膜电阻;阻值:24kΩ;精度:±1%;功率:100mW;工作电压:75V;温度系数:±100ppm/°C;")
      (fields
        (field (name "Manufacturer Part") "0603WAF2402T5E")
        (field (name "Manufacturer") "UNI-ROYAL(厚声)")
      )
      (libsource (lib "easyedapro") (part "0603WAF2402T5E"))
    )
    (comp (ref "R12")
      (value "20kΩ")
      (footprint "easyedapro:R0603")
      (description "电阻类型:厚膜电阻;阻值:24kΩ;精度:±1%;功率:100mW;工作电压:75V;温度系数:±100ppm/°C;")
      (fields
        (field (name "Manufacturer Part") "0603WAF2402T5E")
        (field (name "Manufacturer") "UNI-ROYAL(厚声)")
      )
      (libsource (lib "easyedapro") (part "0603WAF2402T5E"))
    )
    (comp (ref "R14")
      (value "47kΩ")
      (footprint "easyedapro:R0603")
      (description "电阻类型:厚膜电阻;阻值:24kΩ;精度:±1%;功率:100mW;工作电压:75V;温度系数:±100ppm/°C;")
      (fields
        (field (name "Manufacturer Part") "0603WAF2402T5E")
        (field (name "Manufacturer") "UNI-ROYAL(厚声)")
      )
      (libsource (lib "easyedapro") (part "0603WAF2402T5E"))
    )
    (comp (ref "R15")
      (value "10kΩ")
      (footprint "easyedapro:R0603")
      (description "电阻类型:厚膜电阻;阻值:24kΩ;精度:±1%;功率:100mW;工作电压:75V;温度系数:±100ppm/°C;")
      (fields
        (field (name "Manufacturer Part") "0603WAF2402T5E")
        (field (name "Manufacturer") "UNI-ROYAL(厚声)")
      )
      (libsource (lib "easyedapro") (part "0603WAF2402T5E"))
    )
    (comp (ref "R16")
      (value "10K")
      (footprint "easyedapro:R0603")
      (description "电阻类型:厚膜电阻;阻值:24kΩ;精度:±1%;功率:100mW;工作电压:75V;温度系数:±100ppm/°C;")
      (fields
        (field (name "Manufacturer Part") "0603WAF2402T5E")
        (field (name "Manufacturer") "UNI-ROYAL(厚声)")
      )
      (libsource (lib "easyedapro") (part "0603WAF2402T5E"))
    )
    (comp (ref "R17")
      (value "47K")
      (footprint "easyedapro:R0603")
      (description "电阻类型:厚膜电阻;阻值:24kΩ;精度:±1%;功率:100mW;工作电压:75V;温度系数:±100ppm/°C;")
      (fields
        (field (name "Manufacturer Part") "0603WAF2402T5E")
        (field (name "Manufacturer") "UNI-ROYAL(厚声)")
      )
      (libsource (lib "easyedapro") (part "0603WAF2402T5E"))
    )
    (comp (ref "R18")
      (value "47K")
      (footprint "easyedapro:R0603")
      (description "电阻类型:厚膜电阻;阻值:24kΩ;精度:±1%;功率:100mW;工作电压:75V;温度系数:±100ppm/°C;")
      (fields
        (field (name "Manufacturer Part") "0603WAF2402T5E")
        (field (name "Manufacturer") "UNI-ROYAL(厚声)")
      )
      (libsource (lib "easyedapro") (part "0603WAF2402T5E"))
    )
    (comp (ref "R19")
      (value "4.7K")
      (footprint "easyedapro:R0603")
      (description "电阻类型:厚膜电阻;阻值:24kΩ;精度:±1%;功率:100mW;工作电压:75V;温度系数:±100ppm/°C;")
      (fields
        (field (name "Manufacturer Part") "0603WAF2402T5E")
        (field (name "Manufacturer") "UNI-ROYAL(厚声)")
      )
      (libsource (lib "easyedapro") (part "0603WAF2402T5E"))
    )
    (comp (ref "R21")
      (value "470Ω")
      (footprint "easyedapro:R0603")
      (description "电阻类型:厚膜电阻;阻值:24kΩ;精度:±1%;功率:100mW;工作电压:75V;温度系数:±100ppm/°C;")
      (fields
        (field (name "Manufacturer Part") "0603WAF2402T5E")
        (field (name "Manufacturer") "UNI-ROYAL(厚声)")
      )
      (libsource (lib "easyedapro") (part "0603WAF2402T5E"))
    )
    (comp (ref "R22")
      (value "10K")
      (footprint "easyedapro:R0603")
      (description "电阻类型:厚膜电阻;阻值:24kΩ;精度:±1%;功率:100mW;工作电压:75V;温度系数:±100ppm/°C;")
      (fields
        (field (name "Manufacturer Part") "0603WAF2402T5E")
        (field (name "Manufacturer") "UNI-ROYAL(厚声)")
      )
      (libsource (lib "easyedapro") (part "0603WAF2402T5E"))
    )
    (comp (ref "R23")
      (value "470Ω")
      (footprint "easyedapro:R0603")
      (description "电阻类型:厚膜电阻;阻值:24kΩ;精度:±1%;功率:100mW;工作电压:75V;温度系数:±100ppm/°C;")
      (fields
        (field (name "Manufacturer Part") "0603WAF2402T5E")
        (field (name "Manufacturer") "UNI-ROYAL(厚声)")
      )
      (libsource (lib "easyedapro") (part "0603WAF2402T5E"))
    )
    (comp (ref "R24")
      (value "10K")
      (footprint "easyedapro:R0603")
      (description "电阻类型:厚膜电阻;阻值:24kΩ;精度:±1%;功率:100mW;工作电压:75V;温度系数:±100ppm/°C;")
      (fields
        (field (name "Manufacturer Part") "0603WAF2402T5E")
        (field (name "Manufacturer") "UNI-ROYAL(厚声)")
      )
      (libsource (lib "easyedapro") (part "0603WAF2402T5E"))
    )
    (comp (ref "R25")
      (value "10K")
      (footprint "easyedapro:R0603")
      (description "电阻类型:厚膜电阻;阻值:24kΩ;精度:±1%;功率:100mW;工作电压:75V;温度系数:±100ppm/°C;")
      (fields
        (field (name "Manufacturer Part") "0603WAF2402T5E")
        (field (name "Manufacturer") "UNI-ROYAL(厚声)")
      )
      (libsource (lib "easyedapro") (part "0603WAF2402T5E"))
    )
    (comp (ref "R26")
      (value "10K")
      (footprint "easyedapro:R0603")
      (description "电阻类型:厚膜电阻;阻值:24kΩ;精度:±1%;功率:100mW;工作电压:75V;温度系数:±100ppm/°C;")
      (fields
        (field (name "Manufacturer Part") "0603WAF2402T5E")
        (field (name "Manufacturer") "UNI-ROYAL(厚声)")
      )
      (libsource (lib "easyedapro") (part "0603WAF2402T5E"))
    )
    (comp (ref "R27")
      (value "2k")
      (footprint "easyedapro:R0603")
      (description "电阻类型:厚膜电阻;阻值:24kΩ;精度:±1%;功率:100mW;工作电压:75V;温度系数:±100ppm/°C;")
      (fields
        (field (name "Manufacturer Part") "0603WAF2402T5E")
        (field (name "Manufacturer") "UNI-ROYAL(厚声)")
      )
      (libsource (lib "easyedapro") (part "0603WAF2402T5E"))
    )
    (comp (ref "R28")
      (value "2k")
      (footprint "easyedapro:R0603")
      (description "电阻类型:厚膜电阻;阻值:24kΩ;精度:±1%;功率:100mW;工作电压:75V;温度系数:±100ppm/°C;")
      (fields
        (field (name "Manufacturer Part") "0603WAF2402T5E")
        (field (name "Manufacturer") "UNI-ROYAL(厚声)")
      )
      (libsource (lib "easyedapro") (part "0603WAF2402T5E"))
    )
    (comp (ref "R29")
      (value "2k")
      (footprint "easyedapro:R0603")
      (description "电阻类型:厚膜电阻;阻值:24kΩ;精度:±1%;功率:100mW;工作电压:75V;温度系数:±100ppm/°C;")
      (fields
        (field (name "Manufacturer Part") "0603WAF2402T5E")
        (field (name "Manufacturer") "UNI-ROYAL(厚声)")
      )
      (libsource (lib "easyedapro") (part "0603WAF2402T5E"))
    )
    (comp (ref "R30")
      (value "2k")
      (footprint "easyedapro:R0603")
      (description "电阻类型:厚膜电阻;阻值:24kΩ;精度:±1%;功率:100mW;工作电压:75V;温度系数:±100ppm/°C;")
      (fields
        (field (name "Manufacturer Part") "0603WAF2402T5E")
        (field (name "Manufacturer") "UNI-ROYAL(厚声)")
      )
      (libsource (lib "easyedapro") (part "0603WAF2402T5E"))
    )
    (comp (ref "R31")
      (value "10K")
      (footprint "easyedapro:R0603")
      (description "电阻类型:厚膜电阻;阻值:24kΩ;精度:±1%;功率:100mW;工作电压:75V;温度系数:±100ppm/°C;")
      (fields
        (field (name "Manufacturer Part") "0603WAF2402T5E")
        (field (name "Manufacturer") "UNI-ROYAL(厚声)")
      )
      (libsource (lib "easyedapro") (part "0603WAF2402T5E"))
    )
    (comp (ref "R32")
      (value "10K")
      (footprint "easyedapro:R0603")
      (description "电阻类型:厚膜电阻;阻值:24kΩ;精度:±1%;功率:100mW;工作电压:75V;温度系数:±100ppm/°C;")
      (fields
        (field (name "Manufacturer Part") "0603WAF2402T5E")
        (field (name "Manufacturer") "UNI-ROYAL(厚声)")
      )
      (libsource (lib "easyedapro") (part "0603WAF2402T5E"))
    )
    (comp (ref "R33")
      (value "10K")
      (footprint "easyedapro:R0603")
      (description "电阻类型:厚膜电阻;阻值:24kΩ;精度:±1%;功率:100mW;工作电压:75V;温度系数:±100ppm/°C;")
      (fields
        (field (name "Manufacturer Part") "0603WAF2402T5E")
        (field (name "Manufacturer") "UNI-ROYAL(厚声)")
      )
      (libsource (lib "easyedapro") (part "0603WAF2402T5E"))
    )
    (comp (ref "R34")
      (value "0Ω")
      (footprint "easyedapro:R0603")
      (description "电阻类型:厚膜电阻;阻值:24kΩ;精度:±1%;功率:100mW;工作电压:75V;温度系数:±100ppm/°C;")
      (fields
        (field (name "Manufacturer Part") "0603WAF2402T5E")
        (field (name "Manufacturer") "UNI-ROYAL(厚声)")
      )
      (libsource (lib "easyedapro") (part "0603WAF2402T5E"))
    )
    (comp (ref "R35")
      (value "0Ω")
      (footprint "easyedapro:R0603")
      (description "电阻类型:厚膜电阻;阻值:24kΩ;精度:±1%;功率:100mW;工作电压:75V;温度系数:±100ppm/°C;")
      (fields
        (field (name "Manufacturer Part") "0603WAF2402T5E")
        (field (name "Manufacturer") "UNI-ROYAL(厚声)")
      )
      (libsource (lib "easyedapro") (part "0603WAF2402T5E"))
    )
    (comp (ref "R36")
      (value "0Ω")
      (footprint "easyedapro:R0603")
      (description "电阻类型:厚膜电阻;阻值:24kΩ;精度:±1%;功率:100mW;工作电压:75V;温度系数:±100ppm/°C;")
      (fields
        (field (name "Manufacturer Part") "0603WAF2402T5E")
        (field (name "Manufacturer") "UNI-ROYAL(厚声)")
      )
      (libsource (lib "easyedapro") (part "0603WAF2402T5E"))
    )
    (comp (ref "R37")
      (value "0Ω")
      (footprint "easyedapro:R0603")
      (description "电阻类型:厚膜电阻;阻值:24kΩ;精度:±1%;功率:100mW;工作电压:75V;温度系数:±100ppm/°C;")
      (fields
        (field (name "Manufacturer Part") "0603WAF2402T5E")
        (field (name "Manufacturer") "UNI-ROYAL(厚声)")
      )
      (libsource (lib "easyedapro") (part "0603WAF2402T5E"))
    )
    (comp (ref "R38")
      (value "0Ω")
      (footprint "easyedapro:R0603")
      (description "电阻类型:厚膜电阻;阻值:24kΩ;精度:±1%;功率:100mW;工作电压:75V;温度系数:±100ppm/°C;")
      (fields
        (field (name "Manufacturer Part") "0603WAF2402T5E")
        (field (name "Manufacturer") "UNI-ROYAL(厚声)")
      )
      (libsource (lib "easyedapro") (part "0603WAF2402T5E"))
    )
    (comp (ref "R39")
      (value "0Ω")
      (footprint "easyedapro:R0603")
      (description "电阻类型:厚膜电阻;阻值:24kΩ;精度:±1%;功率:100mW;工作电压:75V;温度系数:±100ppm/°C;")
      (fields
        (field (name "Manufacturer Part") "0603WAF2402T5E")
        (field (name "Manufacturer") "UNI-ROYAL(厚声)")
      )
      (libsource (lib "easyedapro") (part "0603WAF2402T5E"))
    )
    (comp (ref "R40")
      (value "2k")
      (footprint "easyedapro:R0603")
      (description "电阻类型:厚膜电阻;阻值:24kΩ;精度:±1%;功率:100mW;工作电压:75V;温度系数:±100ppm/°C;")
      (fields
        (field (name "Manufacturer Part") "0603WAF2402T5E")
        (field (name "Manufacturer") "UNI-ROYAL(厚声)")
      )
      (libsource (lib "easyedapro") (part "0603WAF2402T5E"))
    )
    (comp (ref "R41")
      (value "2k")
      (footprint "easyedapro:R0603")
      (description "电阻类型:厚膜电阻;阻值:24kΩ;精度:±1%;功率:100mW;工作电压:75V;温度系数:±100ppm/°C;")
      (fields
        (field (name "Manufacturer Part") "0603WAF2402T5E")
        (field (name "Manufacturer") "UNI-ROYAL(厚声)")
      )
      (libsource (lib "easyedapro") (part "0603WAF2402T5E"))
    )
    (comp (ref "R42")
      (value "2k")
      (footprint "easyedapro:R0603")
      (description "电阻类型:厚膜电阻;阻值:24kΩ;精度:±1%;功率:100mW;工作电压:75V;温度系数:±100ppm/°C;")
      (fields
        (field (name "Manufacturer Part") "0603WAF2402T5E")
        (field (name "Manufacturer") "UNI-ROYAL(厚声)")
      )
      (libsource (lib "easyedapro") (part "0603WAF2402T5E"))
    )
    (comp (ref "R43")
      (value "2k")
      (footprint "easyedapro:R0603")
      (description "电阻类型:厚膜电阻;阻值:24kΩ;精度:±1%;功率:100mW;工作电压:75V;温度系数:±100ppm/°C;")
      (fields
        (field (name "Manufacturer Part") "0603WAF2402T5E")
        (field (name "Manufacturer") "UNI-ROYAL(厚声)")
      )
      (libsource (lib "easyedapro") (part "0603WAF2402T5E"))
    )
    (comp (ref "R44")
      (value "10K")
      (description "Resistor")
      (fields (field (name "Publisher") "Altium Limited"))
      (libsource (lib "easyedapro") (part "RES"))
    )
    (comp (ref "R45")
      (value "2k")
      (footprint "easyedapro:R0603")
      (description "电阻类型:厚膜电阻;阻值:24kΩ;精度:±1%;功率:100mW;工作电压:75V;温度系数:±100ppm/°C;")
      (fields
        (field (name "Manufacturer Part") "0603WAF2402T5E")
        (field (name "Manufacturer") "UNI-ROYAL(厚声)")
      )
      (libsource (lib "easyedapro") (part "0603WAF2402T5E"))
    )
    (comp (ref "R46")
      (value "2k")
      (footprint "easyedapro:R0603")
      (description "电阻类型:厚膜电阻;阻值:24kΩ;精度:±1%;功率:100mW;工作电压:75V;温度系数:±100ppm/°C;")
      (fields
        (field (name "Manufacturer Part") "0603WAF2402T5E")
        (field (name "Manufacturer") "UNI-ROYAL(厚声)")
      )
      (libsource (lib "easyedapro") (part "0603WAF2402T5E"))
    )
    (comp (ref "R47")
      (value "2k")
      (footprint "easyedapro:R0603")
      (description "电阻类型:厚膜电阻;阻值:24kΩ;精度:±1%;功率:100mW;工作电压:75V;温度系数:±100ppm/°C;")
      (fields
        (field (name "Manufacturer Part") "0603WAF2402T5E")
        (field (name "Manufacturer") "UNI-ROYAL(厚声)")
      )
      (libsource (lib "easyedapro") (part "0603WAF2402T5E"))
    )
    (comp (ref "R48")
      (value "2k")
      (footprint "easyedapro:R0603")
      (description "电阻类型:厚膜电阻;阻值:24kΩ;精度:±1%;功率:100mW;工作电压:75V;温度系数:±100ppm/°C;")
      (fields
        (field (name "Manufacturer Part") "0603WAF2402T5E")
        (field (name "Manufacturer") "UNI-ROYAL(厚声)")
      )
      (libsource (lib "easyedapro") (part "0603WAF2402T5E"))
    )
    (comp (ref "R49")
      (value "10K")
      (description "Resistor")
      (fields (field (name "Publisher") "Altium Limited"))
      (libsource (lib "easyedapro") (part "RES"))
    )
    (comp (ref "R50")
      (value "0Ω")
      (footprint "easyedapro:R0603")
      (description "电阻类型:厚膜电阻;阻值:24kΩ;精度:±1%;功率:100mW;工作电压:75V;温度系数:±100ppm/°C;")
      (fields
        (field (name "Manufacturer Part") "0603WAF2402T5E")
        (field (name "Manufacturer") "UNI-ROYAL(厚声)")
      )
      (libsource (lib "easyedapro") (part "0603WAF2402T5E"))
    )
    (comp (ref "R51")
      (value "10K")
      (footprint "easyedapro:R0603")
      (description "电阻类型:厚膜电阻;阻值:24kΩ;精度:±1%;功率:100mW;工作电压:75V;温度系数:±100ppm/°C;")
      (fields
        (field (name "Manufacturer Part") "0603WAF2402T5E")
        (field (name "Manufacturer") "UNI-ROYAL(厚声)")
      )
      (libsource (lib "easyedapro") (part "0603WAF2402T5E"))
    )
    (comp (ref "R52")
      (value "2k")
      (footprint "easyedapro:R0603")
      (description "电阻类型:厚膜电阻;阻值:24kΩ;精度:±1%;功率:100mW;工作电压:75V;温度系数:±100ppm/°C;")
      (fields
        (field (name "Manufacturer Part") "0603WAF2402T5E")
        (field (name "Manufacturer") "UNI-ROYAL(厚声)")
      )
      (libsource (lib "easyedapro") (part "0603WAF2402T5E"))
    )
    (comp (ref "R53")
      (value "2k")
      (footprint "easyedapro:R0603")
      (description "电阻类型:厚膜电阻;阻值:24kΩ;精度:±1%;功率:100mW;工作电压:75V;温度系数:±100ppm/°C;")
      (fields
        (field (name "Manufacturer Part") "0603WAF2402T5E")
        (field (name "Manufacturer") "UNI-ROYAL(厚声)")
      )
      (libsource (lib "easyedapro") (part "0603WAF2402T5E"))
    )
    (comp (ref "R54")
      (value "2k")
      (footprint "easyedapro:R0603")
      (description "电阻类型:厚膜电阻;阻值:24kΩ;精度:±1%;功率:100mW;工作电压:75V;温度系数:±100ppm/°C;")
      (fields
        (field (name "Manufacturer Part") "0603WAF2402T5E")
        (field (name "Manufacturer") "UNI-ROYAL(厚声)")
      )
      (libsource (lib "easyedapro") (part "0603WAF2402T5E"))
    )
    (comp (ref "R55")
      (value "2k")
      (footprint "easyedapro:R0603")
      (description "电阻类型:厚膜电阻;阻值:24kΩ;精度:±1%;功率:100mW;工作电压:75V;温度系数:±100ppm/°C;")
      (fields
        (field (name "Manufacturer Part") "0603WAF2402T5E")
        (field (name "Manufacturer") "UNI-ROYAL(厚声)")
      )
      (libsource (lib "easyedapro") (part "0603WAF2402T5E"))
    )
    (comp (ref "R56")
      (value "0Ω")
      (footprint "easyedapro:R0603")
      (description "电阻类型:厚膜电阻;阻值:24kΩ;精度:±1%;功率:100mW;工作电压:75V;温度系数:±100ppm/°C;")
      (fields
        (field (name "Manufacturer Part") "0603WAF2402T5E")
        (field (name "Manufacturer") "UNI-ROYAL(厚声)")
      )
      (libsource (lib "easyedapro") (part "0603WAF2402T5E"))
    )
    (comp (ref "R57")
      (value "0Ω")
      (footprint "easyedapro:R0603")
      (description "电阻类型:厚膜电阻;阻值:24kΩ;精度:±1%;功率:100mW;工作电压:75V;温度系数:±100ppm/°C;")
      (fields
        (field (name "Manufacturer Part") "0603WAF2402T5E")
        (field (name "Manufacturer") "UNI-ROYAL(厚声)")
      )
      (libsource (lib "easyedapro") (part "0603WAF2402T5E"))
    )
    (comp (ref "R58")
      (value "10K")
      (footprint "easyedapro:R0603")
      (description "电阻类型:厚膜电阻;阻值:24kΩ;精度:±1%;功率:100mW;工作电压:75V;温度系数:±100ppm/°C;")
      (fields
        (field (name "Manufacturer Part") "0603WAF2402T5E")
        (field (name "Manufacturer") "UNI-ROYAL(厚声)")
      )
      (libsource (lib "easyedapro") (part "0603WAF2402T5E"))
    )
    (comp (ref "R59")
      (value "47K")
      (footprint "easyedapro:10")
      (description "Resistor")
      (libsource (lib "") (part "RES_1"))
    )
    (comp (ref "R60")
      (value "0Ω")
      (footprint "easyedapro:R0603")
      (description "电阻类型:厚膜电阻;阻值:24kΩ;精度:±1%;功率:100mW;工作电压:75V;温度系数:±100ppm/°C;")
      (fields
        (field (name "Manufacturer Part") "0603WAF2402T5E")
        (field (name "Manufacturer") "UNI-ROYAL(厚声)")
      )
      (libsource (lib "easyedapro") (part "0603WAF2402T5E"))
    )
    (comp (ref "R61")
      (value "0Ω")
      (footprint "easyedapro:R0603")
      (description "电阻类型:厚膜电阻;阻值:24kΩ;精度:±1%;功率:100mW;工作电压:75V;温度系数:±100ppm/°C;")
      (fields
        (field (name "Manufacturer Part") "0603WAF2402T5E")
        (field (name "Manufacturer") "UNI-ROYAL(厚声)")
      )
      (libsource (lib "easyedapro") (part "0603WAF2402T5E"))
    )
    (comp (ref "R63")
      (value "0Ω")
      (footprint "easyedapro:R0603")
      (description "电阻类型:厚膜电阻;阻值:24kΩ;精度:±1%;功率:100mW;工作电压:75V;温度系数:±100ppm/°C;")
      (fields
        (field (name "Manufacturer Part") "0603WAF2402T5E")
        (field (name "Manufacturer") "UNI-ROYAL(厚声)")
      )
      (libsource (lib "easyedapro") (part "0603WAF2402T5E"))
    )
    (comp (ref "R65")
      (value "10K")
      (footprint "easyedapro:R0603")
      (description "电阻类型:厚膜电阻;阻值:24kΩ;精度:±1%;功率:100mW;工作电压:75V;温度系数:±100ppm/°C;")
      (fields
        (field (name "Manufacturer Part") "0603WAF2402T5E")
        (field (name "Manufacturer") "UNI-ROYAL(厚声)")
      )
      (libsource (lib "easyedapro") (part "0603WAF2402T5E"))
    )
    (comp (ref "R66")
      (value "0Ω")
      (footprint "easyedapro:R0603")
      (description "电阻类型:厚膜电阻;阻值:24kΩ;精度:±1%;功率:100mW;工作电压:75V;温度系数:±100ppm/°C;")
      (fields
        (field (name "Manufacturer Part") "0603WAF2402T5E")
        (field (name "Manufacturer") "UNI-ROYAL(厚声)")
      )
      (libsource (lib "easyedapro") (part "0603WAF2402T5E"))
    )
    (comp (ref "R67")
      (value "10Ω")
      (footprint "easyedapro:R0603")
      (description "电阻类型:厚膜电阻;阻值:24kΩ;精度:±1%;功率:100mW;工作电压:75V;温度系数:±100ppm/°C;")
      (fields
        (field (name "Manufacturer Part") "0603WAF2402T5E")
        (field (name "Manufacturer") "UNI-ROYAL(厚声)")
      )
      (libsource (lib "easyedapro") (part "0603WAF2402T5E"))
    )
    (comp (ref "R69")
      (value "0Ω")
      (footprint "easyedapro:R0603")
      (description "电阻类型:厚膜电阻;阻值:24kΩ;精度:±1%;功率:100mW;工作电压:75V;温度系数:±100ppm/°C;")
      (fields
        (field (name "Manufacturer Part") "0603WAF2402T5E")
        (field (name "Manufacturer") "UNI-ROYAL(厚声)")
      )
      (libsource (lib "easyedapro") (part "0603WAF2402T5E"))
    )
    (comp (ref "R71")
      (value "47K")
      (footprint "easyedapro:R0603")
      (description "电阻类型:厚膜电阻;阻值:24kΩ;精度:±1%;功率:100mW;工作电压:75V;温度系数:±100ppm/°C;")
      (fields
        (field (name "Manufacturer Part") "0603WAF2402T5E")
        (field (name "Manufacturer") "UNI-ROYAL(厚声)")
      )
      (libsource (lib "easyedapro") (part "0603WAF2402T5E"))
    )
    (comp (ref "U1")
      (value "1117-3.3")
      (footprint "easyedapro:SOT-223")
      (libsource (lib "easyedapro") (part "LM1117"))
    )
    (comp (ref "U2")
      (value "CJ7812")
      (footprint "easyedapro:TO-263-2_L10.1-W9.1-P5.08-LS15.2-TL")
      (description "输出类型:固定;工作电压:35V;输出电压:12V;输出电流:1.5A;电源纹波抑制比(PSRR):71dB@(120Hz);输出极性:正极;")
      (fields (field (name "Manufacturer") "CJ(江苏长电/长晶)"))
      (libsource (lib "easyedapro") (part "CJ7812_C145151"))
    )
    (comp (ref "U3")
      (value "LTV-357T-C")
      (footprint "easyedapro:SOP-4_L4.4-W3.9-P2.54-LS7.0-TL")
      (fields (field (name "Manufacturer") "LITEON(光宝)"))
      (libsource (lib "easyedapro") (part "LTV-357T-C"))
    )
    (comp (ref "U4")
      (value "LTV-357T-C")
      (footprint "easyedapro:SOP-4_L4.4-W3.9-P2.54-LS7.0-TL")
      (fields (field (name "Manufacturer") "LITEON(光宝)"))
      (libsource (lib "easyedapro") (part "LTV-357T-C"))
    )
    (comp (ref "U5")
      (value "XL1509-5.0E1")
      (footprint "easyedapro:SOIC-8_L5.0-W4.0-P1.27-LS6.0-BL")
      (description "功能类型:降压型;同步整流:-;输出通道数:-;拓扑结构:-;输入电压:-;输出电流(最大值):-;开关频率:-;")
      (fields (field (name "Manufacturer") "XLSEMI(芯龙)"))
      (libsource (lib "easyedapro") (part "XL1509-5.0E1"))
    )
    (comp (ref "U6")
      (value "LTV-357T-C")
      (footprint "easyedapro:SOP-4_L4.4-W3.9-P2.54-LS7.0-TL")
      (fields (field (name "Manufacturer") "LITEON(光宝)"))
      (libsource (lib "easyedapro") (part "LTV-357T-C"))
    )
    (comp (ref "U8")
      (value "LTV-357T-C")
      (footprint "easyedapro:SOP-4_L4.4-W3.9-P2.54-LS7.0-TL")
      (fields (field (name "Manufacturer") "LITEON(光宝)"))
      (libsource (lib "easyedapro") (part "LTV-357T-C"))
    )
    (comp (ref "U9")
      (value "LTV-357T-C")
      (footprint "easyedapro:SOP-4_L4.4-W3.9-P2.54-LS7.0-TL")
      (fields (field (name "Manufacturer") "LITEON(光宝)"))
      (libsource (lib "easyedapro") (part "LTV-357T-C"))
    )
    (comp (ref "U10")
      (value "GD32F303CCT6")
      (footprint "easyedapro:LQFP48")
      (description "STM32 ARM-based 32-bit MCU with 32 Kbytes Flash, 48-pin LQFP, Industrial Temperature")
      (libsource (lib "easyedapro") (part "STM32F103C6T6"))
    )
    (comp (ref "U11")
      (value "74LVC1G17")
      (footprint "easyedapro:SMD8")
      (libsource (lib "easyedapro") (part "74LVC1G04"))
    )
    (comp (ref "U12")
      (value "LTV-357T-C")
      (footprint "easyedapro:SOP-4_L4.4-W3.9-P2.54-LS7.0-TL")
      (fields (field (name "Manufacturer") "LITEON(光宝)"))
      (libsource (lib "easyedapro") (part "LTV-357T-C"))
    )
    (comp (ref "U13")
      (value "LTV-357T-C")
      (footprint "easyedapro:SOP-4_L4.4-W3.9-P2.54-LS7.0-TL")
      (fields (field (name "Manufacturer") "LITEON(光宝)"))
      (libsource (lib "easyedapro") (part "LTV-357T-C"))
    )
    (comp (ref "U14")
      (value "XDJK-0051-025")
      (footprint "easyedapro:DC-IN-TH_XDJK-0051-025")
      (description "连接器类型:DC电源插座;安装方式:弯插;触点内径:2.1mm;触点外径:6.3mm;额定电流:3A;额定电压:500V;工作温度:-40°C~+85°C;")
      (fields (field (name "Manufacturer") "LX(连欣科技)"))
      (libsource (lib "easyedapro") (part "XDJK-0051-025"))
    )
    (comp (ref "U15")
      (value "CA-IS3760")
      (footprint "easyedapro:SOIC-16_L9.9-W3.9-P1.27-LS6.0-BL")
      (fields (field (name "Manufacturer") "Chipanalog(川土微)"))
      (libsource (lib "easyedapro") (part "CA-IS3760HN"))
    )
    (comp (ref "U16")
      (value "CH376S")
      (footprint "easyedapro:SOIC-28_L17.9-W7.5-P1.27-LS10.3-BL")
      (description "应用功能:-;USB协议版本:USB 2.0;数据速率:12Mbps;")
      (fields (field (name "Manufacturer") "WCH(南京沁恒)"))
      (libsource (lib "easyedapro") (part "CH376S"))
    )
    (comp (ref "U18")
      (value "74LVC1G17")
      (footprint "easyedapro:SMD8")
      (libsource (lib "easyedapro") (part "74LVC1G04"))
    )
    (comp (ref "U19")
      (value "74LVC1G17")
      (footprint "easyedapro:SMD8")
      (libsource (lib "easyedapro") (part "74LVC1G04"))
    )
    (comp (ref "U20")
      (value "CH340G")
      (fields (field (name "Manufacturer") "WCH(南京沁恒)"))
      (libsource (lib "easyedapro") (part "CH340G"))
    )
    (comp (ref "U21")
      (value "SP3232EEN-L/TR")
      (footprint "easyedapro:SOIC-16_L9.9-W3.9-P1.27-LS6.0-BL")
      (description "类型:收发器;数据速率:235Kbps;")
      (fields (field (name "Manufacturer") "MaxLinear(迈凌)"))
      (libsource (lib "easyedapro") (part "SP3232EEN-L/TR"))
    )
    (comp (ref "U22")
      (value "74LVC1G17")
      (footprint "easyedapro:SOT-23-5_L2.9-W1.6-P0.95-LS2.8-BR")
      (description "输入类型:施密特触发器;工作电压:1.65V~5.5V;元件数:1;每个元件位数:1;灌电流(IOL):24mA;拉电流(IOH):24mA;")
      (fields (field (name "Manufacturer") "TECH PUBLIC(台舟)"))
      (libsource (lib "easyedapro") (part "74LVC1G17W5-TP"))
    )
    (comp (ref "U24")
      (value "GP8101C-SH")
      (footprint "easyedapro:SOIC-8_L4.9-W3.9-P1.27-LS6.0-BL")
      (description "分辨率(位):-;工作电压:11V~32V;接口类型:-;")
      (fields (field (name "Manufacturer") "Guestgood(客益)"))
      (libsource (lib "easyedapro") (part "GP8101C-SH"))
    )
    (comp (ref "USB1")
      (value "U-USBAR04P-F002")
      (footprint "easyedapro:USB-A-TH_USB-302-T")
      (description "连接器类型:Type-A;协议标准:USB 2.0;公母:母;安装方式:弯插;触点数量:4P;端口数量:1;额定电流 - 电源:1.5A;工作温度:0°C~+50°C;")
      (fields (field (name "Manufacturer") "Ckmtw(灿科盟)"))
      (libsource (lib "easyedapro") (part "U-USBAR04P-F001"))
    )
    (comp (ref "USB2")
      (value "TYPE-C 16PIN")
      (footprint "easyedapro:USB-C-SMD_TYPE-C-6PIN-2MD-073")
      (description "连接器类型:Type-C;标准:-;公母:母;端口数量:1;触点数量:16P;安装方式:卧贴;额定电流 - 电源:5A;工作温度范围:-25°C~+85°C;")
      (fields (field (name "Manufacturer") "SHOU HAN(首韩)"))
      (libsource (lib "easyedapro") (part "TYPE-C 16PIN 2MD(073)"))
    )
    (comp (ref "Y1")
      (value "8M")
      (footprint "easyedapro:晶振贴片")
      (description "Crystal Oscillator")
      (libsource (lib "easyedapro") (part "XTAL"))
    )
    (comp (ref "Y2")
      (value "12M")
      (footprint "easyedapro:晶振贴片")
      (description "Crystal Oscillator")
      (libsource (lib "easyedapro") (part "XTAL"))
    )
    (comp (ref "Y3")
      (value "12M")
      (footprint "easyedapro:晶振贴片")
      (description "Crystal Oscillator")
      (libsource (lib "easyedapro") (part "XTAL"))
    )
  )
  (nets
    (net (code "1") (name "/12V") (class "Default")
      (node (ref "C42") (pin "1") (pinfunction "1_1") (pintype "input"))
      (node (ref "C5") (pin "1") (pintype "unspecified"))
      (node (ref "R69") (pin "2") (pinfunction "2_2") (pintype "input"))
      (node (ref "U2") (pin "3") (pinfunction "OUT_3") (pintype "unspecified"))
    )
    (net (code "2") (name "/12V_GP") (class "Default")
      (node (ref "R69") (pin "1") (pinfunction "1_1") (pintype "input"))
      (node (ref "U24") (pin "4") (pinfunction "VCC_4") (pintype "unspecified"))
    )
    (net (code "3") (name "/340_R") (class "Default")
      (node (ref "D14") (pin "2") (pinfunction "A_2") (pintype "unspecified"))
      (node (ref "R58") (pin "1") (pinfunction "1_1") (pintype "input"))
      (node (ref "U20") (pin "3") (pinfunction "RXD_3") (pintype "unspecified"))
    )
    (net (code "4") (name "/340_T") (class "Default")
      (node (ref "D15") (pin "1") (pinfunction "K_1") (pintype "unspecified"))
      (node (ref "U20") (pin "2") (pinfunction "TXD_2") (pintype "unspecified"))
    )
    (net (code "5") (name "/A_1A") (class "Default")
      (node (ref "D32") (pin "1") (pinfunction "1_1") (pintype "unspecified"))
      (node (ref "H11") (pin "4") (pinfunction "4_4") (pintype "unspecified"))
      (node (ref "P16") (pin "3") (pinfunction "3_3") (pintype "unspecified"))
      (node (ref "R54") (pin "2") (pinfunction "2_2") (pintype "input"))
    )
    (net (code "6") (name "/A_1B") (class "Default")
      (node (ref "D33") (pin "1") (pinfunction "1_1") (pintype "unspecified"))
      (node (ref "H11") (pin "3") (pinfunction "3_3") (pintype "unspecified"))
      (node (ref "P16") (pin "4") (pinfunction "4_4") (pintype "unspecified"))
      (node (ref "R55") (pin "2") (pinfunction "2_2") (pintype "input"))
    )
    (net (code "7") (name "/A_2A") (class "Default")
      (node (ref "D31") (pin "1") (pinfunction "1_1") (pintype "unspecified"))
      (node (ref "H11") (pin "5") (pinfunction "5_5") (pintype "unspecified"))
      (node (ref "P16") (pin "2") (pinfunction "2_2") (pintype "unspecified"))
      (node (ref "R53") (pin "2") (pinfunction "2_2") (pintype "input"))
    )
    (net (code "8") (name "/A_2B") (class "Default")
      (node (ref "D30") (pin "1") (pinfunction "1_1") (pintype "unspecified"))
      (node (ref "H11") (pin "6") (pinfunction "6_6") (pintype "unspecified"))
      (node (ref "P16") (pin "1") (pinfunction "1_1") (pintype "unspecified"))
      (node (ref "R52") (pin "2") (pinfunction "2_2") (pintype "input"))
    )
    (net (code "9") (name "/A_DIR_O") (class "Default")
      (node (ref "H10") (pin "1") (pinfunction "1_1") (pintype "unspecified"))
      (node (ref "U19") (pin "4") (pinfunction "Y_4") (pintype "unspecified"))
    )
    (net (code "10") (name "/A_STEP_O") (class "Default")
      (node (ref "H10") (pin "2") (pinfunction "2_2") (pintype "unspecified"))
      (node (ref "U15") (pin "15") (pinfunction "VO1_15") (pintype "unspecified"))
    )
    (net (code "11") (name "/BOOT0") (class "Default")
      (node (ref "R31") (pin "1") (pinfunction "1_1") (pintype "input"))
      (node (ref "U10") (pin "44") (pinfunction "BOOT0_44") (pintype "input"))
    )
    (net (code "12") (name "/BOOT1") (class "Default")
      (node (ref "R32") (pin "1") (pinfunction "1_1") (pintype "input"))
      (node (ref "U10") (pin "20") (pinfunction "PB2/BOOT1_20") (pintype "bidirectional"))
    )
    (net (code "13") (name "/CC1") (class "Default")
      (node (ref "USB2") (pin "4") (pinfunction "CC1_4") (pintype "unspecified"))
    )
    (net (code "14") (name "/CC2") (class "Default")
      (node (ref "USB2") (pin "10") (pinfunction "CC2_10") (pintype "unspecified"))
    )
    (net (code "15") (name "/D1+") (class "Default")
      (node (ref "D12") (pin "3") (pinfunction "I/O2_3") (pintype "unspecified"))
      (node (ref "USB1") (pin "3") (pinfunction "D+_3") (pintype "unspecified"))
    )
    (net (code "16") (name "/D1-") (class "Default")
      (node (ref "D12") (pin "1") (pinfunction "I/O1_1") (pintype "unspecified"))
      (node (ref "USB1") (pin "2") (pinfunction "D-_2") (pintype "unspecified"))
    )
    (net (code "17") (name "/DN-") (class "Default")
      (node (ref "D13") (pin "3") (pinfunction "I/O2_3") (pintype "unspecified"))
      (node (ref "USB2") (pin "5") (pinfunction "DN2_5") (pintype "unspecified"))
      (node (ref "USB2") (pin "7") (pinfunction "DN1_7") (pintype "unspecified"))
    )
    (net (code "18") (name "/DN_D-") (class "Default")
      (node (ref "D13") (pin "4") (pinfunction "I/O2_4") (pintype "unspecified"))
      (node (ref "U20") (pin "6") (pinfunction "UD-_6") (pintype "unspecified"))
    )
    (net (code "19") (name "/DP+") (class "Default")
      (node (ref "D13") (pin "1") (pinfunction "I/O1_1") (pintype "unspecified"))
      (node (ref "USB2") (pin "6") (pinfunction "DP1_6") (pintype "unspecified"))
      (node (ref "USB2") (pin "8") (pinfunction "DP2_8") (pintype "unspecified"))
    )
    (net (code "20") (name "/DP_D+") (class "Default")
      (node (ref "D13") (pin "6") (pinfunction "I/O1_6") (pintype "unspecified"))
      (node (ref "U20") (pin "5") (pinfunction "UD+_5") (pintype "unspecified"))
    )
    (net (code "21") (name "/DTR") (class "Default")
      (node (ref "C30") (pin "2") (pinfunction "2_2") (pintype "input"))
      (node (ref "U20") (pin "13") (pinfunction "DTR#_13") (pintype "unspecified"))
    )
    (net (code "22") (name "/INT") (class "Default")
      (node (ref "R35") (pin "1") (pinfunction "1_1") (pintype "input"))
      (node (ref "U10") (pin "33") (pinfunction "PA12_33") (pintype "bidirectional"))
    )
    (net (code "23") (name "/INT_CH") (class "Default")
      (node (ref "R35") (pin "2") (pinfunction "2_2") (pintype "input"))
      (node (ref "U16") (pin "1") (pinfunction "INT#_1") (pintype "unspecified"))
    )
    (net (code "24") (name "/LASER_CNC") (class "Default")
      (node (ref "R22") (pin "2") (pinfunction "2_2") (pintype "input"))
      (node (ref "U10") (pin "46") (pinfunction "PB9_46") (pintype "bidirectional"))
      (node (ref "U12") (pin "4") (pinfunction "4_4") (pintype "unspecified"))
    )
    (net (code "25") (name "/LA_CNC_SW") (class "Default")
      (node (ref "D11") (pin "2") (pinfunction "2_2") (pintype "input"))
      (node (ref "P11") (pin "1") (pintype "input"))
      (node (ref "P13") (pin "3") (pinfunction "3_3") (pintype "unspecified"))
      (node (ref "U12") (pin "2") (pinfunction "2_2") (pintype "unspecified"))
    )
    (net (code "26") (name "/LED_RUN") (class "Default")
      (node (ref "D9") (pin "2") (pinfunction "2_2") (pintype "unspecified"))
      (node (ref "U10") (pin "38") (pinfunction "PA15/JTDI_38") (pintype "bidirectional"))
    )
    (net (code "27") (name "/MA_DIR") (class "Default")
      (node (ref "R49") (pin "1") (pinfunction "1_1") (pintype "input"))
      (node (ref "U10") (pin "17") (pinfunction "PA7_17") (pintype "bidirectional"))
      (node (ref "U19") (pin "2") (pinfunction "A_2") (pintype "unspecified"))
    )
    (net (code "28") (name "/MA_STEP") (class "Default")
      (node (ref "U10") (pin "16") (pinfunction "PA6_16") (pintype "bidirectional"))
      (node (ref "U15") (pin "2") (pinfunction "VI1_2") (pintype "unspecified"))
    )
    (net (code "29") (name "/MOTOR_EN") (class "Default")
      (node (ref "R26") (pin "2") (pinfunction "2_2") (pintype "input"))
      (node (ref "U10") (pin "28") (pinfunction "PB15_28") (pintype "bidirectional"))
      (node (ref "U11") (pin "2") (pinfunction "A_2") (pintype "unspecified"))
    )
    (net (code "30") (name "/MX_DIR") (class "Default")
      (node (ref "R44") (pin "1") (pinfunction "1_1") (pintype "input"))
      (node (ref "U10") (pin "10") (pinfunction "PA0-WKUP_10") (pintype "bidirectional"))
      (node (ref "U18") (pin "2") (pinfunction "A_2") (pintype "unspecified"))
    )
    (net (code "31") (name "/MX_STEP") (class "Default")
      (node (ref "U10") (pin "11") (pinfunction "PA1_11") (pintype "bidirectional"))
      (node (ref "U15") (pin "7") (pinfunction "VI6_7") (pintype "unspecified"))
    )
    (net (code "32") (name "/MY_DIR") (class "Default")
      (node (ref "U10") (pin "12") (pinfunction "PA2_12") (pintype "bidirectional"))
      (node (ref "U15") (pin "6") (pinfunction "VI5_6") (pintype "unspecified"))
    )
    (net (code "33") (name "/MY_STEP") (class "Default")
      (node (ref "U10") (pin "13") (pinfunction "PA3_13") (pintype "bidirectional"))
      (node (ref "U15") (pin "5") (pinfunction "VI4_5") (pintype "unspecified"))
    )
    (net (code "34") (name "/MZ_DIR") (class "Default")
      (node (ref "U10") (pin "14") (pinfunction "PA4_14") (pintype "bidirectional"))
      (node (ref "U15") (pin "4") (pinfunction "VI3_4") (pintype "unspecified"))
    )
    (net (code "35") (name "/MZ_STEP") (class "Default")
      (node (ref "U10") (pin "15") (pinfunction "PA5_15") (pintype "bidirectional"))
      (node (ref "U15") (pin "3") (pinfunction "VI2_3") (pintype "unspecified"))
    )
    (net (code "36") (name "/M_EN_O") (class "Default")
      (node (ref "H10") (pin "8") (pinfunction "8_8") (pintype "unspecified"))
      (node (ref "H3") (pin "8") (pinfunction "8_8") (pintype "unspecified"))
      (node (ref "H6") (pin "8") (pinfunction "8_8") (pintype "unspecified"))
      (node (ref "H8") (pin "8") (pinfunction "8_8") (pintype "unspecified"))
      (node (ref "U11") (pin "4") (pinfunction "Y_4") (pintype "unspecified"))
    )
    (net (code "37") (name "/NRST") (class "Default")
      (node (ref "C15") (pin "2") (pinfunction "2_2") (pintype "input"))
      (node (ref "R33") (pin "1") (pinfunction "1_1") (pintype "input"))
      (node (ref "U10") (pin "7") (pinfunction "NRST_7") (pintype "bidirectional"))
    )
    (net (code "38") (name "/PB1") (class "Default")
      (node (ref "U10") (pin "19") (pinfunction "PB1_19") (pintype "bidirectional"))
    )
    (net (code "39") (name "/PC13") (class "Default")
      (node (ref "U10") (pin "2") (pinfunction "PC13-TAMPER-RTC_2") (pintype "bidirectional"))
    )
    (net (code "40") (name "/PC14") (class "Default")
      (node (ref "U10") (pin "3") (pinfunction "PC14-OSC32_IN_3") (pintype "bidirectional"))
    )
    (net (code "41") (name "/PC15") (class "Default")
      (node (ref "U10") (pin "4") (pinfunction "PC15-OSC32_OUT_4") (pintype "bidirectional"))
    )
    (net (code "42") (name "/PROBE") (class "Default")
      (node (ref "R24") (pin "2") (pinfunction "2_2") (pintype "input"))
      (node (ref "U10") (pin "18") (pinfunction "PB0_18") (pintype "bidirectional"))
      (node (ref "U13") (pin "4") (pinfunction "4_4") (pintype "unspecified"))
    )
    (net (code "43") (name "/PROBE_OUT") (class "Default")
      (node (ref "D10") (pin "2") (pinfunction "2_2") (pintype "input"))
      (node (ref "D8") (pin "1") (pinfunction "K_1") (pintype "unspecified"))
      (node (ref "H2") (pin "1") (pinfunction "1_1") (pintype "unspecified"))
      (node (ref "U14") (pin "1") (pinfunction "1_1") (pintype "unspecified"))
    )
    (net (code "44") (name "/PWM_3V3") (class "Default")
      (node (ref "R63") (pin "1") (pinfunction "1_1") (pintype "input"))
      (node (ref "R9") (pin "2") (pinfunction "2_2") (pintype "input"))
      (node (ref "U10") (pin "29") (pinfunction "PA8_29") (pintype "bidirectional"))
      (node (ref "U22") (pin "2") (pinfunction "A_2") (pintype "unspecified"))
    )
    (net (code "45") (name "/PWM_5V") (class "Default")
      (node (ref "CN1") (pin "1") (pinfunction "1_1") (pintype "unspecified"))
      (node (ref "D16") (pin "1") (pinfunction "1_1") (pintype "input"))
      (node (ref "U22") (pin "4") (pinfunction "Y_4") (pintype "unspecified"))
    )
    (net (code "46") (name "/PWM_10V") (class "Default")
      (node (ref "D38") (pin "1") (pinfunction "K_1") (pintype "unspecified"))
      (node (ref "P4") (pin "2") (pinfunction "2_2") (pintype "unspecified"))
      (node (ref "R67") (pin "2") (pinfunction "2_2") (pintype "input"))
    )
    (net (code "47") (name "/PWM_GP") (class "Default")
      (node (ref "R65") (pin "1") (pinfunction "1_1") (pintype "input"))
      (node (ref "U24") (pin "3") (pinfunction "PWM_3") (pintype "unspecified"))
      (node (ref "U6") (pin "3") (pinfunction "3_3") (pintype "unspecified"))
    )
    (net (code "48") (name "/R1IN") (class "Default")
      (node (ref "U21") (pin "13") (pinfunction "R1IN_13") (pintype "unspecified"))
    )
    (net (code "49") (name "/R1OUT") (class "Default")
      (node (ref "U21") (pin "12") (pinfunction "R1OUT_12") (pintype "unspecified"))
    )
    (net (code "50") (name "/R2IN") (class "Default")
      (node (ref "P17") (pin "2") (pinfunction "D-_2") (pintype "unspecified"))
      (node (ref "U21") (pin "8") (pinfunction "R2IN_8") (pintype "unspecified"))
    )
    (net (code "51") (name "/R2OUT") (class "Default")
      (node (ref "R61") (pin "1") (pinfunction "1_1") (pintype "input"))
      (node (ref "U21") (pin "9") (pinfunction "R2OUT_9") (pintype "unspecified"))
    )
    (net (code "52") (name "/RS232_VCC") (class "Default")
      (node (ref "C33") (pin "2") (pinfunction "2_2") (pintype "input"))
      (node (ref "R56") (pin "1") (pinfunction "1_1") (pintype "input"))
      (node (ref "R57") (pin "1") (pinfunction "1_1") (pintype "input"))
      (node (ref "U21") (pin "16") (pinfunction "VCC_16") (pintype "unspecified"))
    )
    (net (code "53") (name "/RSTI") (class "Default")
      (node (ref "R34") (pin "2") (pinfunction "2_2") (pintype "input"))
      (node (ref "U16") (pin "2") (pinfunction "RSTI_2") (pintype "unspecified"))
    )
    (net (code "54") (name "/RST_340") (class "Default")
      (node (ref "C30") (pin "1") (pinfunction "1_1") (pintype "input"))
      (node (ref "U10") (pin "45") (pinfunction "PB8_45") (pintype "bidirectional"))
    )
    (net (code "55") (name "/RST_376") (class "Default")
      (node (ref "R34") (pin "1") (pinfunction "1_1") (pintype "input"))
      (node (ref "U10") (pin "43") (pinfunction "PB7_43") (pintype "bidirectional"))
    )
    (net (code "56") (name "/RXD1") (class "Default")
      (node (ref "D15") (pin "2") (pinfunction "A_2") (pintype "unspecified"))
      (node (ref "R51") (pin "1") (pinfunction "1_1") (pintype "input"))
      (node (ref "U10") (pin "31") (pinfunction "PA10_31") (pintype "bidirectional"))
    )
    (net (code "57") (name "/RXD3") (class "Default")
      (node (ref "H5") (pin "2") (pinfunction "2_2") (pintype "unspecified"))
      (node (ref "R61") (pin "2") (pinfunction "2_2") (pintype "input"))
      (node (ref "U10") (pin "22") (pinfunction "PB11_22") (pintype "bidirectional"))
    )
    (net (code "58") (name "/SCK") (class "Default")
      (node (ref "R39") (pin "1") (pinfunction "1_1") (pintype "input"))
      (node (ref "U16") (pin "20") (pinfunction "SCK/D5_20") (pintype "unspecified"))
    )
    (net (code "59") (name "/SDI") (class "Default")
      (node (ref "R38") (pin "1") (pinfunction "1_1") (pintype "input"))
      (node (ref "U16") (pin "21") (pinfunction "SDI/D6_21") (pintype "unspecified"))
    )
    (net (code "60") (name "/SDO") (class "Default")
      (node (ref "R37") (pin "1") (pinfunction "1_1") (pintype "input"))
      (node (ref "U16") (pin "22") (pinfunction "SDO/D7_22") (pintype "unspecified"))
    )
    (net (code "61") (name "/SM_XC") (class "Default")
      (node (ref "R17") (pin "2") (pinfunction "2_2") (pintype "input"))
      (node (ref "U10") (pin "32") (pinfunction "PA11_32") (pintype "bidirectional"))
      (node (ref "U8") (pin "1") (pinfunction "1_1") (pintype "unspecified"))
    )
    (net (code "62") (name "/SM_XC_OUT") (class "Default")
      (node (ref "P7") (pin "2") (pinfunction "2_2") (pintype "unspecified"))
      (node (ref "R16") (pin "1") (pinfunction "1_1") (pintype "input"))
      (node (ref "U8") (pin "4") (pinfunction "4_4") (pintype "unspecified"))
    )
    (net (code "63") (name "/SPI1_CS") (class "Default")
      (node (ref "U10") (pin "42") (pinfunction "PB6_42") (pintype "bidirectional"))
      (node (ref "U16") (pin "18") (pinfunction "SCS/D3_18") (pintype "unspecified"))
    )
    (net (code "64") (name "/SPI1_MISO") (class "Default")
      (node (ref "R37") (pin "2") (pinfunction "2_2") (pintype "input"))
      (node (ref "U10") (pin "40") (pinfunction "PB4/JNTRST_40") (pintype "bidirectional"))
    )
    (net (code "65") (name "/SPI1_MOSI") (class "Default")
      (node (ref "R38") (pin "2") (pinfunction "2_2") (pintype "input"))
      (node (ref "U10") (pin "41") (pinfunction "PB5_41") (pintype "bidirectional"))
    )
    (net (code "66") (name "/SPI1_SCK") (class "Default")
      (node (ref "R39") (pin "2") (pinfunction "2_2") (pintype "input"))
      (node (ref "U10") (pin "39") (pinfunction "PB3/JTDO_39") (pintype "bidirectional"))
    )
    (net (code "67") (name "/SWCLK") (class "Default")
      (node (ref "H1") (pin "3") (pinfunction "3_3") (pintype "unspecified"))
      (node (ref "U10") (pin "37") (pinfunction "PA14/JTCK/SWCLK_37") (pintype "bidirectional"))
    )
    (net (code "68") (name "/SWDIO") (class "Default")
      (node (ref "H1") (pin "4") (pinfunction "4_4") (pintype "unspecified"))
      (node (ref "U10") (pin "34") (pinfunction "PA13/JTMS/SWDIO_34") (pintype "bidirectional"))
    )
    (net (code "69") (name "/T1IN") (class "Default")
      (node (ref "U21") (pin "11") (pinfunction "T1IN_11") (pintype "unspecified"))
    )
    (net (code "70") (name "/T1OUT") (class "Default")
      (node (ref "U21") (pin "14") (pinfunction "T1OUT_14") (pintype "unspecified"))
    )
    (net (code "71") (name "/T2IN") (class "Default")
      (node (ref "R60") (pin "1") (pinfunction "1_1") (pintype "input"))
      (node (ref "U21") (pin "10") (pinfunction "T2IN_10") (pintype "unspecified"))
    )
    (net (code "72") (name "/T2OUT") (class "Default")
      (node (ref "P17") (pin "3") (pinfunction "D+_3") (pintype "unspecified"))
      (node (ref "U21") (pin "7") (pinfunction "T2OUT_7") (pintype "unspecified"))
    )
    (net (code "73") (name "/TXD1") (class "Default")
      (node (ref "D14") (pin "1") (pinfunction "K_1") (pintype "unspecified"))
      (node (ref "U10") (pin "30") (pinfunction "PA9_30") (pintype "bidirectional"))
    )
    (net (code "74") (name "/TXD3") (class "Default")
      (node (ref "H5") (pin "1") (pinfunction "1_1") (pintype "unspecified"))
      (node (ref "R60") (pin "2") (pinfunction "2_2") (pintype "input"))
      (node (ref "U10") (pin "21") (pinfunction "PB10_21") (pintype "bidirectional"))
    )
    (net (code "75") (name "/U_D+") (class "Default")
      (node (ref "D12") (pin "4") (pinfunction "I/O2_4") (pintype "unspecified"))
      (node (ref "U16") (pin "10") (pinfunction "UD+_10") (pintype "unspecified"))
    )
    (net (code "76") (name "/U_D-") (class "Default")
      (node (ref "D12") (pin "6") (pinfunction "I/O1_6") (pintype "unspecified"))
      (node (ref "U16") (pin "11") (pinfunction "UD-_11") (pintype "unspecified"))
    )
    (net (code "77") (name "/XTAL1") (class "Default")
      (node (ref "C9") (pin "2") (pinfunction "2_2") (pintype "input"))
      (node (ref "U10") (pin "5") (pinfunction "OSC_IN/PD0_5") (pintype "input"))
      (node (ref "Y1") (pin "1") (pinfunction "OSC1_1") (pintype "unspecified"))
    )
    (net (code "78") (name "/XTAL2") (class "Default")
      (node (ref "C8") (pin "2") (pinfunction "2_2") (pintype "input"))
      (node (ref "U10") (pin "6") (pinfunction "OSC_OUT/PD1_6") (pintype "output"))
      (node (ref "Y1") (pin "2") (pinfunction "OSC2_2") (pintype "unspecified"))
    )
    (net (code "79") (name "/X_1A") (class "Default")
      (node (ref "D20") (pin "1") (pinfunction "1_1") (pintype "unspecified"))
      (node (ref "H4") (pin "4") (pinfunction "4_4") (pintype "unspecified"))
      (node (ref "P12") (pin "3") (pinfunction "3_3") (pintype "unspecified"))
      (node (ref "R29") (pin "2") (pinfunction "2_2") (pintype "input"))
    )
    (net (code "80") (name "/X_1B") (class "Default")
      (node (ref "D21") (pin "1") (pinfunction "1_1") (pintype "unspecified"))
      (node (ref "H4") (pin "3") (pinfunction "3_3") (pintype "unspecified"))
      (node (ref "P12") (pin "4") (pinfunction "4_4") (pintype "unspecified"))
      (node (ref "R30") (pin "2") (pinfunction "2_2") (pintype "input"))
    )
    (net (code "81") (name "/X_2A") (class "Default")
      (node (ref "D19") (pin "1") (pinfunction "1_1") (pintype "unspecified"))
      (node (ref "H4") (pin "5") (pinfunction "5_5") (pintype "unspecified"))
      (node (ref "P12") (pin "2") (pinfunction "2_2") (pintype "unspecified"))
      (node (ref "R28") (pin "2") (pinfunction "2_2") (pintype "input"))
    )
    (net (code "82") (name "/X_2B") (class "Default")
      (node (ref "D18") (pin "1") (pinfunction "1_1") (pintype "unspecified"))
      (node (ref "H4") (pin "6") (pinfunction "6_6") (pintype "unspecified"))
      (node (ref "P12") (pin "1") (pinfunction "1_1") (pintype "unspecified"))
      (node (ref "R27") (pin "2") (pinfunction "2_2") (pintype "input"))
    )
    (net (code "83") (name "/X_DIR_O") (class "Default")
      (node (ref "H3") (pin "1") (pinfunction "1_1") (pintype "unspecified"))
      (node (ref "U18") (pin "4") (pinfunction "Y_4") (pintype "unspecified"))
    )
    (net (code "84") (name "/X_LIMT") (class "Default")
      (node (ref "R1") (pin "2") (pinfunction "2_2") (pintype "input"))
      (node (ref "U10") (pin "27") (pinfunction "PB14_27") (pintype "bidirectional"))
      (node (ref "U3") (pin "4") (pinfunction "4_4") (pintype "unspecified"))
    )
    (net (code "85") (name "/X_LIMT_I") (class "Default")
      (node (ref "P1") (pin "1") (pinfunction "1_1") (pintype "unspecified"))
      (node (ref "P2") (pin "1") (pinfunction "1_1") (pintype "unspecified"))
      (node (ref "U3") (pin "2") (pinfunction "2_2") (pintype "unspecified"))
    )
    (net (code "86") (name "/X_STEP_O") (class "Default")
      (node (ref "H3") (pin "2") (pinfunction "2_2") (pintype "unspecified"))
      (node (ref "U15") (pin "10") (pinfunction "VO6_10") (pintype "unspecified"))
    )
    (net (code "87") (name "/Y_1A") (class "Default")
      (node (ref "D28") (pin "1") (pinfunction "1_1") (pintype "unspecified"))
      (node (ref "H7") (pin "4") (pinfunction "4_4") (pintype "unspecified"))
      (node (ref "P14") (pin "3") (pinfunction "3_3") (pintype "unspecified"))
      (node (ref "R42") (pin "2") (pinfunction "2_2") (pintype "input"))
    )
    (net (code "88") (name "/Y_1B") (class "Default")
      (node (ref "D29") (pin "1") (pinfunction "1_1") (pintype "unspecified"))
      (node (ref "H7") (pin "3") (pinfunction "3_3") (pintype "unspecified"))
      (node (ref "P14") (pin "4") (pinfunction "4_4") (pintype "unspecified"))
      (node (ref "R43") (pin "2") (pinfunction "2_2") (pintype "input"))
    )
    (net (code "89") (name "/Y_2A") (class "Default")
      (node (ref "D27") (pin "1") (pinfunction "1_1") (pintype "unspecified"))
      (node (ref "H7") (pin "5") (pinfunction "5_5") (pintype "unspecified"))
      (node (ref "P14") (pin "2") (pinfunction "2_2") (pintype "unspecified"))
      (node (ref "R41") (pin "2") (pinfunction "2_2") (pintype "input"))
    )
    (net (code "90") (name "/Y_2B") (class "Default")
      (node (ref "D26") (pin "1") (pinfunction "1_1") (pintype "unspecified"))
      (node (ref "H7") (pin "6") (pinfunction "6_6") (pintype "unspecified"))
      (node (ref "P14") (pin "1") (pinfunction "1_1") (pintype "unspecified"))
      (node (ref "R40") (pin "2") (pinfunction "2_2") (pintype "input"))
    )
    (net (code "91") (name "/Y_DIR_O") (class "Default")
      (node (ref "H6") (pin "1") (pinfunction "1_1") (pintype "unspecified"))
      (node (ref "U15") (pin "11") (pinfunction "VO5_11") (pintype "unspecified"))
    )
    (net (code "92") (name "/Y_LIMT") (class "Default")
      (node (ref "R5") (pin "2") (pinfunction "2_2") (pintype "input"))
      (node (ref "U10") (pin "26") (pinfunction "PB13_26") (pintype "bidirectional"))
      (node (ref "U4") (pin "4") (pinfunction "4_4") (pintype "unspecified"))
    )
    (net (code "93") (name "/Y_LIMT_I") (class "Default")
      (node (ref "P3") (pin "1") (pinfunction "1_1") (pintype "unspecified"))
      (node (ref "P5") (pin "1") (pinfunction "1_1") (pintype "unspecified"))
      (node (ref "U4") (pin "2") (pinfunction "2_2") (pintype "unspecified"))
    )
    (net (code "94") (name "/Y_STEP_O") (class "Default")
      (node (ref "H6") (pin "2") (pinfunction "2_2") (pintype "unspecified"))
      (node (ref "U15") (pin "12") (pinfunction "VO4_12") (pintype "unspecified"))
    )
    (net (code "95") (name "/Z_1A") (class "Default")
      (node (ref "D24") (pin "1") (pinfunction "1_1") (pintype "unspecified"))
      (node (ref "H9") (pin "4") (pinfunction "4_4") (pintype "unspecified"))
      (node (ref "P15") (pin "3") (pinfunction "3_3") (pintype "unspecified"))
      (node (ref "R47") (pin "2") (pinfunction "2_2") (pintype "input"))
    )
    (net (code "96") (name "/Z_1B") (class "Default")
      (node (ref "D25") (pin "1") (pinfunction "1_1") (pintype "unspecified"))
      (node (ref "H9") (pin "3") (pinfunction "3_3") (pintype "unspecified"))
      (node (ref "P15") (pin "4") (pinfunction "4_4") (pintype "unspecified"))
      (node (ref "R48") (pin "2") (pinfunction "2_2") (pintype "input"))
    )
    (net (code "97") (name "/Z_2A") (class "Default")
      (node (ref "D23") (pin "1") (pinfunction "1_1") (pintype "unspecified"))
      (node (ref "H9") (pin "5") (pinfunction "5_5") (pintype "unspecified"))
      (node (ref "P15") (pin "2") (pinfunction "2_2") (pintype "unspecified"))
      (node (ref "R46") (pin "2") (pinfunction "2_2") (pintype "input"))
    )
    (net (code "98") (name "/Z_2B") (class "Default")
      (node (ref "D22") (pin "1") (pinfunction "1_1") (pintype "unspecified"))
      (node (ref "H9") (pin "6") (pinfunction "6_6") (pintype "unspecified"))
      (node (ref "P15") (pin "1") (pinfunction "1_1") (pintype "unspecified"))
      (node (ref "R45") (pin "2") (pinfunction "2_2") (pintype "input"))
    )
    (net (code "99") (name "/Z_DIR_O") (class "Default")
      (node (ref "H8") (pin "1") (pinfunction "1_1") (pintype "unspecified"))
      (node (ref "U15") (pin "13") (pinfunction "VO3_13") (pintype "unspecified"))
    )
    (net (code "100") (name "/Z_LIMT") (class "Default")
      (node (ref "R18") (pin "2") (pinfunction "2_2") (pintype "input"))
      (node (ref "U10") (pin "25") (pinfunction "PB12_25") (pintype "bidirectional"))
      (node (ref "U9") (pin "4") (pinfunction "4_4") (pintype "unspecified"))
    )
    (net (code "101") (name "/Z_LIMT_I") (class "Default")
      (node (ref "P6") (pin "1") (pinfunction "1_1") (pintype "unspecified"))
      (node (ref "P8") (pin "1") (pinfunction "1_1") (pintype "unspecified"))
      (node (ref "U9") (pin "2") (pinfunction "2_2") (pintype "unspecified"))
    )
    (net (code "102") (name "/Z_STEP_O") (class "Default")
      (node (ref "H8") (pin "2") (pinfunction "2_2") (pintype "unspecified"))
      (node (ref "U15") (pin "14") (pinfunction "VO2_14") (pintype "unspecified"))
    )
    (net (code "103") (name "3V3") (class "Default")
      (node (ref "C1") (pin "1") (pinfunction "1_1") (pintype "input"))
      (node (ref "C17") (pin "1") (pinfunction "1_1") (pintype "input"))
      (node (ref "C18") (pin "1") (pinfunction "1_1") (pintype "input"))
      (node (ref "C19") (pin "1") (pinfunction "1_1") (pintype "input"))
      (node (ref "C2") (pin "2") (pinfunction "2_2") (pintype "input"))
      (node (ref "C20") (pin "1") (pinfunction "1_1") (pintype "input"))
      (node (ref "H1") (pin "2") (pinfunction "2_2") (pintype "unspecified"))
      (node (ref "R1") (pin "1") (pinfunction "1_1") (pintype "input"))
      (node (ref "R17") (pin "1") (pinfunction "1_1") (pintype "input"))
      (node (ref "R18") (pin "1") (pinfunction "1_1") (pintype "input"))
      (node (ref "R22") (pin "1") (pinfunction "1_1") (pintype "input"))
      (node (ref "R24") (pin "1") (pinfunction "1_1") (pintype "input"))
      (node (ref "R25") (pin "1") (pinfunction "1_1") (pintype "input"))
      (node (ref "R26") (pin "1") (pinfunction "1_1") (pintype "input"))
      (node (ref "R33") (pin "2") (pinfunction "2_2") (pintype "input"))
      (node (ref "R5") (pin "1") (pinfunction "1_1") (pintype "input"))
      (node (ref "R51") (pin "2") (pinfunction "2_2") (pintype "input"))
      (node (ref "R56") (pin "2") (pinfunction "2_2") (pintype "input"))
      (node (ref "R9") (pin "1") (pinfunction "1_1") (pintype "input"))
      (node (ref "U1") (pin "2") (pinfunction "OUT_2") (pintype "unspecified"))
      (node (ref "U1") (pin "4") (pinfunction "=_4") (pintype "unspecified"))
      (node (ref "U10") (pin "24") (pinfunction "VDD_1_24") (pintype "unspecified"))
      (node (ref "U10") (pin "36") (pinfunction "VDD_2_36") (pintype "unspecified"))
      (node (ref "U10") (pin "48") (pinfunction "VDD_3_48") (pintype "unspecified"))
      (node (ref "U10") (pin "9") (pinfunction "VDDA_9") (pintype "unspecified"))
      (node (ref "U15") (pin "1") (pinfunction "VDDA_1") (pintype "unspecified"))
      (node (ref "U16") (pin "28") (pinfunction "VCC_28") (pintype "unspecified"))
      (node (ref "U16") (pin "9") (pinfunction "V3_9") (pintype "unspecified"))
    )
    (net (code "104") (name "5V_USB") (class "Default")
      (node (ref "D13") (pin "5") (pinfunction "VBUS_5") (pintype "unspecified"))
      (node (ref "R50") (pin "1") (pinfunction "1_1") (pintype "input"))
      (node (ref "R59") (pin "1") (pinfunction "1_1") (pintype "unspecified"))
      (node (ref "USB2") (pin "11") (pinfunction "VBUS_11") (pintype "unspecified"))
      (node (ref "USB2") (pin "2") (pinfunction "VBUS_2") (pintype "unspecified"))
    )
    (net (code "105") (name "5V_VCC") (class "Default")
      (node (ref "C10") (pin "2") (pinfunction "2_2") (pintype "unspecified"))
      (node (ref "C11") (pin "1") (pinfunction "1_1") (pintype "input"))
      (node (ref "C13") (pin "2") (pinfunction "2_2") (pintype "unspecified"))
      (node (ref "C22") (pin "2") (pinfunction "2_2") (pintype "unspecified"))
      (node (ref "C23") (pin "1") (pinfunction "1_1") (pintype "input"))
      (node (ref "C26") (pin "2") (pinfunction "2_2") (pintype "unspecified"))
      (node (ref "C28") (pin "1") (pinfunction "1_1") (pintype "input"))
      (node (ref "C3") (pin "1") (pinfunction "1_1") (pintype "input"))
      (node (ref "C38") (pin "2") (pinfunction "2_2") (pintype "input"))
      (node (ref "D12") (pin "5") (pinfunction "VBUS_5") (pintype "unspecified"))
      (node (ref "D6") (pin "2") (pinfunction "2_2") (pintype "input"))
      (node (ref "H10") (pin "5") (pinfunction "5_5") (pintype "unspecified"))
      (node (ref "H10") (pin "6") (pinfunction "6_6") (pintype "unspecified"))
      (node (ref "H10") (pin "7") (pinfunction "7_7") (pintype "unspecified"))
      (node (ref "H11") (pin "2") (pinfunction "2_2") (pintype "unspecified"))
      (node (ref "H3") (pin "5") (pinfunction "5_5") (pintype "unspecified"))
      (node (ref "H3") (pin "6") (pinfunction "6_6") (pintype "unspecified"))
      (node (ref "H3") (pin "7") (pinfunction "7_7") (pintype "unspecified"))
      (node (ref "H4") (pin "2") (pinfunction "2_2") (pintype "unspecified"))
      (node (ref "H6") (pin "5") (pinfunction "5_5") (pintype "unspecified"))
      (node (ref "H6") (pin "6") (pinfunction "6_6") (pintype "unspecified"))
      (node (ref "H6") (pin "7") (pinfunction "7_7") (pintype "unspecified"))
      (node (ref "H7") (pin "2") (pinfunction "2_2") (pintype "unspecified"))
      (node (ref "H8") (pin "5") (pinfunction "5_5") (pintype "unspecified"))
      (node (ref "H8") (pin "6") (pinfunction "6_6") (pintype "unspecified"))
      (node (ref "H8") (pin "7") (pinfunction "7_7") (pintype "unspecified"))
      (node (ref "H9") (pin "2") (pinfunction "2_2") (pintype "unspecified"))
      (node (ref "L1") (pin "1") (pinfunction "1_1") (pintype "unspecified"))
      (node (ref "R12") (pin "2") (pinfunction "2_2") (pintype "input"))
      (node (ref "R21") (pin "1") (pinfunction "1_1") (pintype "input"))
      (node (ref "R23") (pin "1") (pinfunction "1_1") (pintype "input"))
      (node (ref "R4") (pin "1") (pinfunction "1_1") (pintype "input"))
      (node (ref "R50") (pin "2") (pinfunction "2_2") (pintype "input"))
      (node (ref "R57") (pin "2") (pinfunction "2_2") (pintype "input"))
      (node (ref "R58") (pin "2") (pinfunction "2_2") (pintype "input"))
      (node (ref "R66") (pin "1") (pinfunction "1_1") (pintype "input"))
      (node (ref "R71") (pin "1") (pinfunction "1_1") (pintype "input"))
      (node (ref "U1") (pin "3") (pinfunction "IN_3") (pintype "unspecified"))
      (node (ref "U11") (pin "5") (pinfunction "VCC_5") (pintype "unspecified"))
      (node (ref "U15") (pin "16") (pinfunction "VDDB_16") (pintype "unspecified"))
      (node (ref "U18") (pin "5") (pinfunction "VCC_5") (pintype "unspecified"))
      (node (ref "U19") (pin "5") (pinfunction "VCC_5") (pintype "unspecified"))
      (node (ref "U20") (pin "16") (pinfunction "VCC_16") (pintype "unspecified"))
      (node (ref "U22") (pin "5") (pinfunction "VCC_5") (pintype "unspecified"))
      (node (ref "U24") (pin "8") (pinfunction "V5V_8") (pintype "unspecified"))
      (node (ref "U5") (pin "3") (pinfunction "FB_3") (pintype "input"))
      (node (ref "USB1") (pin "1") (pinfunction "VCC_1") (pintype "unspecified"))
    )
    (net (code "106") (name "24V_D1") (class "Default")
      (node (ref "C6") (pin "1") (pintype "unspecified"))
      (node (ref "C7") (pin "1") (pinfunction "1_1") (pintype "unspecified"))
      (node (ref "D2") (pin "2") (pinfunction "2_2") (pintype "unspecified"))
      (node (ref "R3") (pin "1") (pinfunction "1_1") (pintype "input"))
      (node (ref "U5") (pin "1") (pinfunction "VIN_1") (pintype "input"))
    )
    (net (code "107") (name "24V_D2") (class "Default")
      (node (ref "C14") (pin "1") (pintype "unspecified"))
      (node (ref "C16") (pin "1") (pintype "unspecified"))
      (node (ref "C25") (pin "1") (pintype "unspecified"))
      (node (ref "C27") (pin "1") (pintype "unspecified"))
      (node (ref "D7") (pin "2") (pinfunction "2_2") (pintype "unspecified"))
      (node (ref "H11") (pin "8") (pinfunction "8_8") (pintype "unspecified"))
      (node (ref "H4") (pin "8") (pinfunction "8_8") (pintype "unspecified"))
      (node (ref "H7") (pin "8") (pinfunction "8_8") (pintype "unspecified"))
      (node (ref "H9") (pin "8") (pinfunction "8_8") (pintype "unspecified"))
    )
    (net (code "108") (name "24V_D4") (class "Default")
      (node (ref "C4") (pin "1") (pintype "unspecified"))
      (node (ref "CN1") (pin "3") (pinfunction "3_3") (pintype "unspecified"))
      (node (ref "D37") (pin "2") (pinfunction "2_2") (pintype "unspecified"))
      (node (ref "P17") (pin "1") (pinfunction "VBUS_1") (pintype "unspecified"))
      (node (ref "R16") (pin "2") (pinfunction "2_2") (pintype "input"))
      (node (ref "U2") (pin "1") (pinfunction "IN_1") (pintype "unspecified"))
    )
    (net (code "109") (name "24V_SW") (class "Default")
      (node (ref "P10") (pin "2") (pinfunction "2_2") (pintype "unspecified"))
      (node (ref "P9") (pin "1") (pinfunction "1_1") (pintype "unspecified"))
    )
    (net (code "110") (name "24V_VCC") (class "Default")
      (node (ref "C12") (pin "1") (pintype "unspecified"))
      (node (ref "D17") (pin "1") (pinfunction "K_1") (pintype "unspecified"))
      (node (ref "D2") (pin "1") (pinfunction "1_1") (pintype "unspecified"))
      (node (ref "D37") (pin "1") (pinfunction "1_1") (pintype "unspecified"))
      (node (ref "D7") (pin "1") (pinfunction "1_1") (pintype "unspecified"))
      (node (ref "P10") (pin "1") (pinfunction "1_1") (pintype "unspecified"))
      (node (ref "R14") (pin "2") (pinfunction "2_2") (pintype "input"))
    )
    (net (code "111") (name "GND") (class "Default")
      (node (ref "C1") (pin "2") (pinfunction "2_2") (pintype "input"))
      (node (ref "C10") (pin "1") (pinfunction "1_1") (pintype "unspecified"))
      (node (ref "C11") (pin "2") (pinfunction "2_2") (pintype "input"))
      (node (ref "C12") (pin "2") (pintype "unspecified"))
      (node (ref "C13") (pin "1") (pinfunction "1_1") (pintype "unspecified"))
      (node (ref "C14") (pin "2") (pintype "unspecified"))
      (node (ref "C15") (pin "1") (pinfunction "1_1") (pintype "input"))
      (node (ref "C16") (pin "2") (pintype "unspecified"))
      (node (ref "C17") (pin "2") (pinfunction "2_2") (pintype "input"))
      (node (ref "C18") (pin "2") (pinfunction "2_2") (pintype "input"))
      (node (ref "C19") (pin "2") (pinfunction "2_2") (pintype "input"))
      (node (ref "C2") (pin "1") (pinfunction "1_1") (pintype "input"))
      (node (ref "C20") (pin "2") (pinfunction "2_2") (pintype "input"))
      (node (ref "C21") (pin "1") (pinfunction "1_1") (pintype "input"))
      (node (ref "C22") (pin "1") (pinfunction "1_1") (pintype "unspecified"))
      (node (ref "C23") (pin "2") (pinfunction "2_2") (pintype "input"))
      (node (ref "C24") (pin "1") (pinfunction "1_1") (pintype "input"))
      (node (ref "C25") (pin "2") (pintype "unspecified"))
      (node (ref "C26") (pin "1") (pinfunction "1_1") (pintype "unspecified"))
      (node (ref "C27") (pin "2") (pintype "unspecified"))
      (node (ref "C28") (pin "2") (pinfunction "2_2") (pintype "input"))
      (node (ref "C29") (pin "2") (pinfunction "2_2") (pintype "input"))
      (node (ref "C3") (pin "2") (pinfunction "2_2") (pintype "input"))
      (node (ref "C31") (pin "1") (pinfunction "1_1") (pintype "input"))
      (node (ref "C33") (pin "1") (pinfunction "1_1") (pintype "input"))
      (node (ref "C34") (pin "1") (pinfunction "1_1") (pintype "input"))
      (node (ref "C36") (pin "2") (pinfunction "2_2") (pintype "input"))
      (node (ref "C37") (pin "1") (pinfunction "1_1") (pintype "input"))
      (node (ref "C38") (pin "1") (pinfunction "1_1") (pintype "input"))
      (node (ref "C4") (pin "2") (pintype "unspecified"))
      (node (ref "C42") (pin "2") (pinfunction "2_2") (pintype "input"))
      (node (ref "C5") (pin "2") (pintype "unspecified"))
      (node (ref "C6") (pin "2") (pintype "unspecified"))
      (node (ref "C7") (pin "2") (pinfunction "2_2") (pintype "unspecified"))
      (node (ref "C8") (pin "1") (pinfunction "1_1") (pintype "input"))
      (node (ref "C9") (pin "1") (pinfunction "1_1") (pintype "input"))
      (node (ref "CN1") (pin "2") (pinfunction "2_2") (pintype "unspecified"))
      (node (ref "D10") (pin "1") (pinfunction "1_1") (pintype "input"))
      (node (ref "D11") (pin "1") (pinfunction "1_1") (pintype "input"))
      (node (ref "D12") (pin "2") (pinfunction "GND_2") (pintype "unspecified"))
      (node (ref "D13") (pin "2") (pinfunction "GND_2") (pintype "unspecified"))
      (node (ref "D16") (pin "2") (pinfunction "2_2") (pintype "input"))
      (node (ref "D17") (pin "2") (pinfunction "A_2") (pintype "unspecified"))
      (node (ref "D18") (pin "2") (pinfunction "2_2") (pintype "unspecified"))
      (node (ref "D19") (pin "2") (pinfunction "2_2") (pintype "unspecified"))
      (node (ref "D20") (pin "2") (pinfunction "2_2") (pintype "unspecified"))
      (node (ref "D21") (pin "2") (pinfunction "2_2") (pintype "unspecified"))
      (node (ref "D22") (pin "2") (pinfunction "2_2") (pintype "unspecified"))
      (node (ref "D23") (pin "2") (pinfunction "2_2") (pintype "unspecified"))
      (node (ref "D24") (pin "2") (pinfunction "2_2") (pintype "unspecified"))
      (node (ref "D25") (pin "2") (pinfunction "2_2") (pintype "unspecified"))
      (node (ref "D26") (pin "2") (pinfunction "2_2") (pintype "unspecified"))
      (node (ref "D27") (pin "2") (pinfunction "2_2") (pintype "unspecified"))
      (node (ref "D28") (pin "2") (pinfunction "2_2") (pintype "unspecified"))
      (node (ref "D29") (pin "2") (pinfunction "2_2") (pintype "unspecified"))
      (node (ref "D30") (pin "2") (pinfunction "2_2") (pintype "unspecified"))
      (node (ref "D31") (pin "2") (pinfunction "2_2") (pintype "unspecified"))
      (node (ref "D32") (pin "2") (pinfunction "2_2") (pintype "unspecified"))
      (node (ref "D33") (pin "2") (pinfunction "2_2") (pintype "unspecified"))
      (node (ref "D38") (pin "2") (pinfunction "A_2") (pintype "unspecified"))
      (node (ref "D5") (pin "1") (pinfunction "1_1") (pintype "unspecified"))
      (node (ref "D6") (pin "1") (pinfunction "1_1") (pintype "input"))
      (node (ref "DC1") (pin "2") (pinfunction "2_2") (pintype "unspecified"))
      (node (ref "DC1") (pin "3") (pinfunction "3_3") (pintype "unspecified"))
      (node (ref "H1") (pin "1") (pinfunction "1_1") (pintype "unspecified"))
      (node (ref "H11") (pin "1") (pinfunction "1_1") (pintype "unspecified"))
      (node (ref "H11") (pin "7") (pinfunction "7_7") (pintype "unspecified"))
      (node (ref "H2") (pin "2") (pinfunction "2_2") (pintype "unspecified"))
      (node (ref "H4") (pin "1") (pinfunction "1_1") (pintype "unspecified"))
      (node (ref "H4") (pin "7") (pinfunction "7_7") (pintype "unspecified"))
      (node (ref "H7") (pin "1") (pinfunction "1_1") (pintype "unspecified"))
      (node (ref "H7") (pin "7") (pinfunction "7_7") (pintype "unspecified"))
      (node (ref "H9") (pin "1") (pinfunction "1_1") (pintype "unspecified"))
      (node (ref "H9") (pin "7") (pinfunction "7_7") (pintype "unspecified"))
      (node (ref "LED1") (pin "1") (pinfunction "K_1") (pintype "unspecified"))
      (node (ref "LED2") (pin "1") (pinfunction "K_1") (pintype "unspecified"))
      (node (ref "LED3") (pin "1") (pinfunction "K_1") (pintype "unspecified"))
      (node (ref "P1") (pin "2") (pinfunction "2_2") (pintype "unspecified"))
      (node (ref "P11") (pin "2") (pintype "input"))
      (node (ref "P13") (pin "1") (pinfunction "1_1") (pintype "unspecified"))
      (node (ref "P13") (pin "2") (pinfunction "2_2") (pintype "unspecified"))
      (node (ref "P17") (pin "4") (pinfunction "GND_4") (pintype "unspecified"))
      (node (ref "P17") (pin "5") (pinfunction "GND_5") (pintype "unspecified"))
      (node (ref "P17") (pin "6") (pinfunction "GND_6") (pintype "unspecified"))
      (node (ref "P2") (pin "2") (pinfunction "2_2") (pintype "unspecified"))
      (node (ref "P3") (pin "2") (pinfunction "2_2") (pintype "unspecified"))
      (node (ref "P4") (pin "1") (pinfunction "1_1") (pintype "unspecified"))
      (node (ref "P5") (pin "2") (pinfunction "2_2") (pintype "unspecified"))
      (node (ref "P6") (pin "2") (pinfunction "2_2") (pintype "unspecified"))
      (node (ref "P7") (pin "1") (pinfunction "1_1") (pintype "unspecified"))
      (node (ref "P8") (pin "2") (pinfunction "2_2") (pintype "unspecified"))
      (node (ref "R15") (pin "1") (pinfunction "1_1") (pintype "input"))
      (node (ref "R27") (pin "1") (pinfunction "1_1") (pintype "input"))
      (node (ref "R28") (pin "1") (pinfunction "1_1") (pintype "input"))
      (node (ref "R29") (pin "1") (pinfunction "1_1") (pintype "input"))
      (node (ref "R30") (pin "1") (pinfunction "1_1") (pintype "input"))
      (node (ref "R31") (pin "2") (pinfunction "2_2") (pintype "input"))
      (node (ref "R32") (pin "2") (pinfunction "2_2") (pintype "input"))
      (node (ref "R40") (pin "1") (pinfunction "1_1") (pintype "input"))
      (node (ref "R41") (pin "1") (pinfunction "1_1") (pintype "input"))
      (node (ref "R42") (pin "1") (pinfunction "1_1") (pintype "input"))
      (node (ref "R43") (pin "1") (pinfunction "1_1") (pintype "input"))
      (node (ref "R44") (pin "2") (pinfunction "2_2") (pintype "input"))
      (node (ref "R45") (pin "1") (pinfunction "1_1") (pintype "input"))
      (node (ref "R46") (pin "1") (pinfunction "1_1") (pintype "input"))
      (node (ref "R47") (pin "1") (pinfunction "1_1") (pintype "input"))
      (node (ref "R48") (pin "1") (pinfunction "1_1") (pintype "input"))
      (node (ref "R49") (pin "2") (pinfunction "2_2") (pintype "input"))
      (node (ref "R52") (pin "1") (pinfunction "1_1") (pintype "input"))
      (node (ref "R53") (pin "1") (pinfunction "1_1") (pintype "input"))
      (node (ref "R54") (pin "1") (pinfunction "1_1") (pintype "input"))
      (node (ref "R55") (pin "1") (pinfunction "1_1") (pintype "input"))
      (node (ref "R65") (pin "2") (pinfunction "2_2") (pintype "input"))
      (node (ref "U1") (pin "1") (pinfunction "GND_1") (pintype "unspecified"))
      (node (ref "U10") (pin "23") (pinfunction "VSS_1_23") (pintype "unspecified"))
      (node (ref "U10") (pin "35") (pinfunction "VSS_2_35") (pintype "unspecified"))
      (node (ref "U10") (pin "47") (pinfunction "VSS_3_47") (pintype "unspecified"))
      (node (ref "U10") (pin "8") (pinfunction "VSSA_8") (pintype "unspecified"))
      (node (ref "U11") (pin "3") (pinfunction "GND_3") (pintype "unspecified"))
      (node (ref "U12") (pin "3") (pinfunction "3_3") (pintype "unspecified"))
      (node (ref "U13") (pin "3") (pinfunction "3_3") (pintype "unspecified"))
      (node (ref "U14") (pin "2") (pinfunction "2_2") (pintype "unspecified"))
      (node (ref "U14") (pin "3") (pinfunction "3_3") (pintype "unspecified"))
      (node (ref "U15") (pin "8") (pinfunction "GNDA_8") (pintype "unspecified"))
      (node (ref "U15") (pin "9") (pinfunction "GNDB_9") (pintype "unspecified"))
      (node (ref "U16") (pin "12") (pinfunction "GND_12") (pintype "unspecified"))
      (node (ref "U18") (pin "3") (pinfunction "GND_3") (pintype "unspecified"))
      (node (ref "U19") (pin "3") (pinfunction "GND_3") (pintype "unspecified"))
      (node (ref "U2") (pin "2") (pinfunction "TAB_2") (pintype "unspecified"))
      (node (ref "U20") (pin "1") (pinfunction "GND_1") (pintype "unspecified"))
      (node (ref "U21") (pin "15") (pinfunction "GND_15") (pintype "unspecified"))
      (node (ref "U22") (pin "3") (pinfunction "GND_3") (pintype "unspecified"))
      (node (ref "U24") (pin "5") (pinfunction "GND_5") (pintype "unspecified"))
      (node (ref "U3") (pin "3") (pinfunction "3_3") (pintype "unspecified"))
      (node (ref "U4") (pin "3") (pinfunction "3_3") (pintype "unspecified"))
      (node (ref "U5") (pin "5") (pinfunction "GND_5") (pintype "input"))
      (node (ref "U5") (pin "6") (pinfunction "GND_6") (pintype "input"))
      (node (ref "U5") (pin "7") (pinfunction "GND_7") (pintype "input"))
      (node (ref "U5") (pin "8") (pinfunction "GND_8") (pintype "input"))
      (node (ref "U6") (pin "2") (pinfunction "2_2") (pintype "unspecified"))
      (node (ref "U8") (pin "2") (pinfunction "2_2") (pintype "unspecified"))
      (node (ref "U8") (pin "3") (pinfunction "3_3") (pintype "unspecified"))
      (node (ref "U9") (pin "3") (pinfunction "3_3") (pintype "unspecified"))
      (node (ref "USB1") (pin "4") (pinfunction "GND_4") (pintype "unspecified"))
      (node (ref "USB1") (pin "5") (pinfunction "SH1_5") (pintype "unspecified"))
      (node (ref "USB1") (pin "6") (pinfunction "SH2_6") (pintype "unspecified"))
      (node (ref "USB2") (pin "1") (pinfunction "GND_1") (pintype "unspecified"))
      (node (ref "USB2") (pin "12") (pinfunction "GND_12") (pintype "unspecified"))
      (node (ref "USB2") (pin "13") (pinfunction "SHELL_13") (pintype "unspecified"))
      (node (ref "USB2") (pin "14") (pinfunction "SHELL_14") (pintype "unspecified"))
    )
    (net (code "112") (name "Net-(D8-A)") (class "Default")
      (node (ref "D8") (pin "2") (pinfunction "A_2") (pintype "unspecified"))
      (node (ref "U13") (pin "2") (pinfunction "2_2") (pintype "unspecified"))
    )
    (net (code "113") (name "Net-(D9-Pad1)") (class "Default")
      (node (ref "D9") (pin "1") (pinfunction "1_1") (pintype "unspecified"))
      (node (ref "R25") (pin "2") (pinfunction "2_2") (pintype "input"))
    )
    (net (code "114") (name "Net-(H3-Pad3)") (class "Default")
      (node (ref "H3") (pin "3") (pinfunction "3_3") (pintype "unspecified"))
      (node (ref "H3") (pin "4") (pinfunction "4_4") (pintype "unspecified"))
    )
    (net (code "115") (name "Net-(H6-Pad3)") (class "Default")
      (node (ref "H6") (pin "3") (pinfunction "3_3") (pintype "unspecified"))
      (node (ref "H6") (pin "4") (pinfunction "4_4") (pintype "unspecified"))
    )
    (net (code "116") (name "Net-(H8-Pad3)") (class "Default")
      (node (ref "H8") (pin "3") (pinfunction "3_3") (pintype "unspecified"))
      (node (ref "H8") (pin "4") (pinfunction "4_4") (pintype "unspecified"))
    )
    (net (code "117") (name "Net-(H10-Pad3)") (class "Default")
      (node (ref "H10") (pin "3") (pinfunction "3_3") (pintype "unspecified"))
      (node (ref "H10") (pin "4") (pinfunction "4_4") (pintype "unspecified"))
    )
    (net (code "118") (name "Net-(LED1-A)") (class "Default")
      (node (ref "LED1") (pin "2") (pinfunction "A_2") (pintype "unspecified"))
      (node (ref "R12") (pin "1") (pinfunction "1_1") (pintype "input"))
    )
    (net (code "119") (name "Net-(LED2-A)") (class "Default")
      (node (ref "LED2") (pin "2") (pinfunction "A_2") (pintype "unspecified"))
      (node (ref "R14") (pin "1") (pinfunction "1_1") (pintype "input"))
    )
    (net (code "120") (name "Net-(LED3-A)") (class "Default")
      (node (ref "LED3") (pin "2") (pinfunction "A_2") (pintype "unspecified"))
      (node (ref "R59") (pin "2") (pinfunction "2_2") (pintype "unspecified"))
    )
    (net (code "121") (name "Net-(R2-Pad2)") (class "Default")
      (node (ref "R2") (pin "2") (pinfunction "2_2") (pintype "input"))
      (node (ref "U3") (pin "1") (pinfunction "1_1") (pintype "unspecified"))
    )
    (net (code "122") (name "Net-(R6-Pad2)") (class "Default")
      (node (ref "R6") (pin "2") (pinfunction "2_2") (pintype "input"))
      (node (ref "U4") (pin "1") (pinfunction "1_1") (pintype "unspecified"))
    )
    (net (code "123") (name "Net-(R19-Pad2)") (class "Default")
      (node (ref "R19") (pin "2") (pinfunction "2_2") (pintype "input"))
      (node (ref "U9") (pin "1") (pinfunction "1_1") (pintype "unspecified"))
    )
    (net (code "124") (name "Net-(R21-Pad2)") (class "Default")
      (node (ref "R21") (pin "2") (pinfunction "2_2") (pintype "input"))
      (node (ref "U12") (pin "1") (pinfunction "1_1") (pintype "unspecified"))
    )
    (net (code "125") (name "Net-(R23-Pad2)") (class "Default")
      (node (ref "R23") (pin "2") (pinfunction "2_2") (pintype "input"))
      (node (ref "U13") (pin "1") (pinfunction "1_1") (pintype "unspecified"))
    )
    (net (code "126") (name "Net-(R63-Pad2)") (class "Default")
      (node (ref "R63") (pin "2") (pinfunction "2_2") (pintype "input"))
      (node (ref "U6") (pin "1") (pinfunction "1_1") (pintype "unspecified"))
    )
    (net (code "127") (name "Net-(R71-Pad2)") (class "Default")
      (node (ref "R71") (pin "2") (pinfunction "2_2") (pintype "input"))
      (node (ref "U6") (pin "4") (pinfunction "4_4") (pintype "unspecified"))
    )
    (net (code "128") (name "Net-(U5-ON{slash}OFF)") (class "Default")
      (node (ref "R15") (pin "2") (pinfunction "2_2") (pintype "input"))
      (node (ref "U5") (pin "4") (pinfunction "ON/OFF_4") (pintype "input"))
    )
    (net (code "129") (name "Net-(U5-OUTPUT)") (class "Default")
      (node (ref "D5") (pin "2") (pinfunction "2_2") (pintype "unspecified"))
      (node (ref "L1") (pin "2") (pinfunction "2_2") (pintype "unspecified"))
      (node (ref "U5") (pin "2") (pinfunction "OUTPUT_2") (pintype "input"))
    )
    (net (code "130") (name "Net-(U16-ACT#)") (class "Default")
      (node (ref "R36") (pin "1") (pinfunction "1_1") (pintype "input"))
      (node (ref "U16") (pin "24") (pinfunction "ACT#_24") (pintype "unspecified"))
    )
    (net (code "131") (name "Net-(U16-XI)") (class "Default")
      (node (ref "C21") (pin "2") (pinfunction "2_2") (pintype "input"))
      (node (ref "U16") (pin "13") (pinfunction "XI_13") (pintype "unspecified"))
      (node (ref "Y2") (pin "2") (pinfunction "OSC2_2") (pintype "unspecified"))
    )
    (net (code "132") (name "Net-(U16-XO)") (class "Default")
      (node (ref "C24") (pin "2") (pinfunction "2_2") (pintype "input"))
      (node (ref "U16") (pin "14") (pinfunction "XO_14") (pintype "unspecified"))
      (node (ref "Y2") (pin "1") (pinfunction "OSC1_1") (pintype "unspecified"))
    )
    (net (code "133") (name "Net-(U20-V3)") (class "Default")
      (node (ref "C29") (pin "1") (pinfunction "1_1") (pintype "input"))
      (node (ref "U20") (pin "4") (pinfunction "V3_4") (pintype "unspecified"))
    )
    (net (code "134") (name "Net-(U20-XI)") (class "Default")
      (node (ref "C34") (pin "2") (pinfunction "2_2") (pintype "input"))
      (node (ref "U20") (pin "7") (pinfunction "XI_7") (pintype "unspecified"))
      (node (ref "Y3") (pin "2") (pinfunction "OSC2_2") (pintype "unspecified"))
    )
    (net (code "135") (name "Net-(U20-XO)") (class "Default")
      (node (ref "C37") (pin "2") (pinfunction "2_2") (pintype "input"))
      (node (ref "U20") (pin "8") (pinfunction "XO_8") (pintype "unspecified"))
      (node (ref "Y3") (pin "1") (pinfunction "OSC1_1") (pintype "unspecified"))
    )
    (net (code "136") (name "Net-(U21-C1+)") (class "Default")
      (node (ref "C32") (pin "1") (pinfunction "1_1") (pintype "input"))
      (node (ref "U21") (pin "1") (pinfunction "C1+_1") (pintype "unspecified"))
    )
    (net (code "137") (name "Net-(U21-C1-)") (class "Default")
      (node (ref "C32") (pin "2") (pinfunction "2_2") (pintype "input"))
      (node (ref "U21") (pin "3") (pinfunction "C1-_3") (pintype "unspecified"))
    )
    (net (code "138") (name "Net-(U21-C2+)") (class "Default")
      (node (ref "C35") (pin "1") (pinfunction "1_1") (pintype "input"))
      (node (ref "U21") (pin "4") (pinfunction "C2+_4") (pintype "unspecified"))
    )
    (net (code "139") (name "Net-(U21-C2-)") (class "Default")
      (node (ref "C35") (pin "2") (pinfunction "2_2") (pintype "input"))
      (node (ref "U21") (pin "5") (pinfunction "C2-_5") (pintype "unspecified"))
    )
    (net (code "140") (name "Net-(U21-V+)") (class "Default")
      (node (ref "C31") (pin "2") (pinfunction "2_2") (pintype "input"))
      (node (ref "U21") (pin "2") (pinfunction "V+_2") (pintype "unspecified"))
    )
    (net (code "141") (name "Net-(U21-V-)") (class "Default")
      (node (ref "C36") (pin "1") (pinfunction "1_1") (pintype "input"))
      (node (ref "U21") (pin "6") (pinfunction "V-_6") (pintype "unspecified"))
    )
    (net (code "142") (name "Net-(U24-EN)") (class "Default")
      (node (ref "R66") (pin "2") (pinfunction "2_2") (pintype "input"))
      (node (ref "U24") (pin "2") (pinfunction "EN_2") (pintype "unspecified"))
    )
    (net (code "143") (name "Net-(U24-VOUT)") (class "Default")
      (node (ref "R67") (pin "1") (pinfunction "1_1") (pintype "input"))
      (node (ref "U24") (pin "6") (pinfunction "VOUT_6") (pintype "unspecified"))
    )
    (net (code "144") (name "VCC_LIMT") (class "Default")
      (node (ref "P1") (pin "3") (pinfunction "3_3") (pintype "unspecified"))
      (node (ref "P2") (pin "3") (pinfunction "3_3") (pintype "unspecified"))
      (node (ref "P3") (pin "3") (pinfunction "3_3") (pintype "unspecified"))
      (node (ref "P5") (pin "3") (pinfunction "3_3") (pintype "unspecified"))
      (node (ref "P6") (pin "3") (pinfunction "3_3") (pintype "unspecified"))
      (node (ref "P8") (pin "3") (pinfunction "3_3") (pintype "unspecified"))
      (node (ref "R19") (pin "1") (pinfunction "1_1") (pintype "input"))
      (node (ref "R2") (pin "1") (pinfunction "1_1") (pintype "input"))
      (node (ref "R3") (pin "2") (pinfunction "2_2") (pintype "input"))
      (node (ref "R4") (pin "2") (pinfunction "2_2") (pintype "input"))
      (node (ref "R6") (pin "1") (pinfunction "1_1") (pintype "input"))
    )
    (net (code "145") (name "VIN24V") (class "Default")
      (node (ref "DC1") (pin "1") (pinfunction "1_1") (pintype "unspecified"))
      (node (ref "P9") (pin "2") (pinfunction "2_2") (pintype "unspecified"))
    )
    (net (code "146") (name "unconnected-(R36-Pad2)") (class "Default")
      (node (ref "R36") (pin "2") (pinfunction "2_2") (pintype "input"))
    )
    (net (code "147") (name "unconnected-(U10-VBAT-Pad1)") (class "Default")
      (node (ref "U10") (pin "1") (pinfunction "VBAT_1") (pintype "unspecified"))
    )
    (net (code "148") (name "unconnected-(U11-NC-Pad1)") (class "Default")
      (node (ref "U11") (pin "1") (pinfunction "NC_1") (pintype "unspecified"))
    )
    (net (code "149") (name "unconnected-(U16-A0-Pad8)") (class "Default")
      (node (ref "U16") (pin "8") (pinfunction "A0_8") (pintype "unspecified"))
    )
    (net (code "150") (name "unconnected-(U16-BZ{slash}D4-Pad19)") (class "Default")
      (node (ref "U16") (pin "19") (pinfunction "BZ/D4_19") (pintype "unspecified"))
    )
    (net (code "151") (name "unconnected-(U16-D0-Pad15)") (class "Default")
      (node (ref "U16") (pin "15") (pinfunction "D0_15") (pintype "unspecified"))
    )
    (net (code "152") (name "unconnected-(U16-D1-Pad16)") (class "Default")
      (node (ref "U16") (pin "16") (pinfunction "D1_16") (pintype "unspecified"))
    )
    (net (code "153") (name "unconnected-(U16-D2-Pad17)") (class "Default")
      (node (ref "U16") (pin "17") (pinfunction "D2_17") (pintype "unspecified"))
    )
    (net (code "154") (name "unconnected-(U16-PCS#-Pad27)") (class "Default")
      (node (ref "U16") (pin "27") (pinfunction "PCS#_27") (pintype "unspecified"))
    )
    (net (code "155") (name "unconnected-(U16-RD#-Pad4)") (class "Default")
      (node (ref "U16") (pin "4") (pinfunction "RD#_4") (pintype "unspecified"))
    )
    (net (code "156") (name "unconnected-(U16-RXD-Pad6)") (class "Default")
      (node (ref "U16") (pin "6") (pinfunction "RXD_6") (pintype "unspecified"))
    )
    (net (code "157") (name "unconnected-(U16-SD-CK-Pad26)") (class "Default")
      (node (ref "U16") (pin "26") (pinfunction "SD-CK_26") (pintype "unspecified"))
    )
    (net (code "158") (name "unconnected-(U16-SD-CS-Pad23)") (class "Default")
      (node (ref "U16") (pin "23") (pinfunction "SD-CS_23") (pintype "unspecified"))
    )
    (net (code "159") (name "unconnected-(U16-SD-DO-Pad25)") (class "Default")
      (node (ref "U16") (pin "25") (pinfunction "SD-DO_25") (pintype "unspecified"))
    )
    (net (code "160") (name "unconnected-(U16-SD_DI-Pad7)") (class "Default")
      (node (ref "U16") (pin "7") (pinfunction "SD_DI_7") (pintype "unspecified"))
    )
    (net (code "161") (name "unconnected-(U16-TXD-Pad5)") (class "Default")
      (node (ref "U16") (pin "5") (pinfunction "TXD_5") (pintype "unspecified"))
    )
    (net (code "162") (name "unconnected-(U16-WR#-Pad3)") (class "Default")
      (node (ref "U16") (pin "3") (pinfunction "WR#_3") (pintype "unspecified"))
    )
    (net (code "163") (name "unconnected-(U18-NC-Pad1)") (class "Default")
      (node (ref "U18") (pin "1") (pinfunction "NC_1") (pintype "unspecified"))
    )
    (net (code "164") (name "unconnected-(U19-NC-Pad1)") (class "Default")
      (node (ref "U19") (pin "1") (pinfunction "NC_1") (pintype "unspecified"))
    )
    (net (code "165") (name "unconnected-(U20-CTS#-Pad9)") (class "Default")
      (node (ref "U20") (pin "9") (pinfunction "CTS#_9") (pintype "unspecified"))
    )
    (net (code "166") (name "unconnected-(U20-DCD#-Pad12)") (class "Default")
      (node (ref "U20") (pin "12") (pinfunction "DCD#_12") (pintype "unspecified"))
    )
    (net (code "167") (name "unconnected-(U20-DSR#-Pad10)") (class "Default")
      (node (ref "U20") (pin "10") (pinfunction "DSR#_10") (pintype "unspecified"))
    )
    (net (code "168") (name "unconnected-(U20-R232-Pad15)") (class "Default")
      (node (ref "U20") (pin "15") (pinfunction "R232_15") (pintype "unspecified"))
    )
    (net (code "169") (name "unconnected-(U20-RI#-Pad11)") (class "Default")
      (node (ref "U20") (pin "11") (pinfunction "RI#_11") (pintype "unspecified"))
    )
    (net (code "170") (name "unconnected-(U20-RTS#-Pad14)") (class "Default")
      (node (ref "U20") (pin "14") (pinfunction "RTS#_14") (pintype "unspecified"))
    )
    (net (code "171") (name "unconnected-(U22-NC-Pad1)") (class "Default")
      (node (ref "U22") (pin "1") (pinfunction "NC_1") (pintype "unspecified"))
    )
    (net (code "172") (name "unconnected-(U24-NC-Pad1)") (class "Default")
      (node (ref "U24") (pin "1") (pinfunction "NC_1") (pintype "unspecified+no_connect"))
    )
    (net (code "173") (name "unconnected-(U24-NC-Pad7)") (class "Default")
      (node (ref "U24") (pin "7") (pinfunction "NC_7") (pintype "unspecified+no_connect"))
    )
    (net (code "174") (name "unconnected-(USB2-SBU1-Pad9)") (class "Default")
      (node (ref "USB2") (pin "9") (pinfunction "SBU1_9") (pintype "unspecified+no_connect"))
    )
    (net (code "175") (name "unconnected-(USB2-SBU2-Pad3)") (class "Default")
      (node (ref "USB2") (pin "3") (pinfunction "SBU2_3") (pintype "unspecified+no_connect"))
    )
  )
)
